# zx80_SD_12_smd_build006_5_STM32.net
KiCad netlist of a schematic drawn in EAGLE
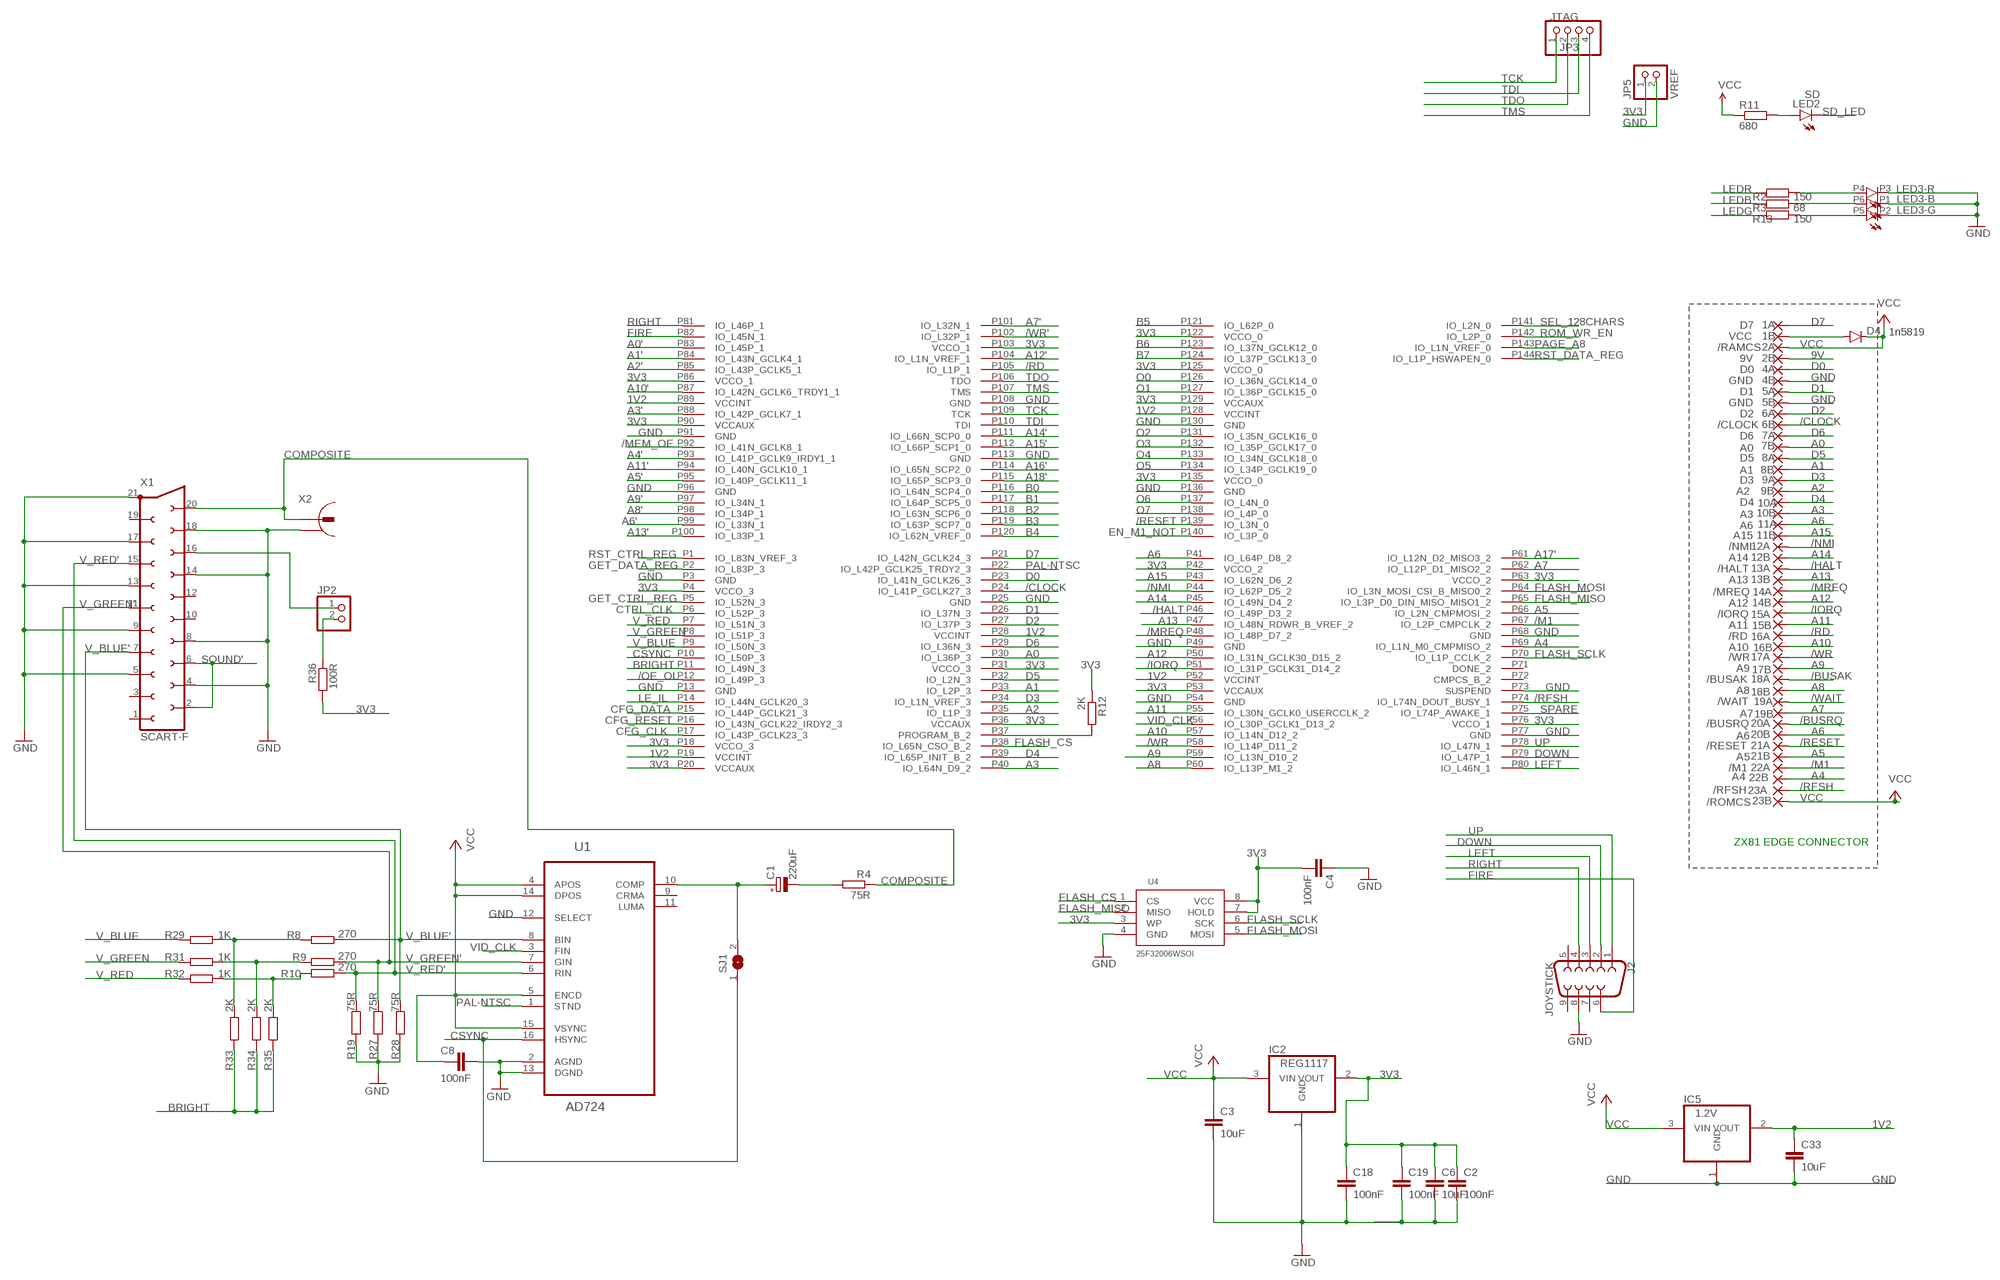
[diagram p0: schematic, sheet 1, part 1 of 2]
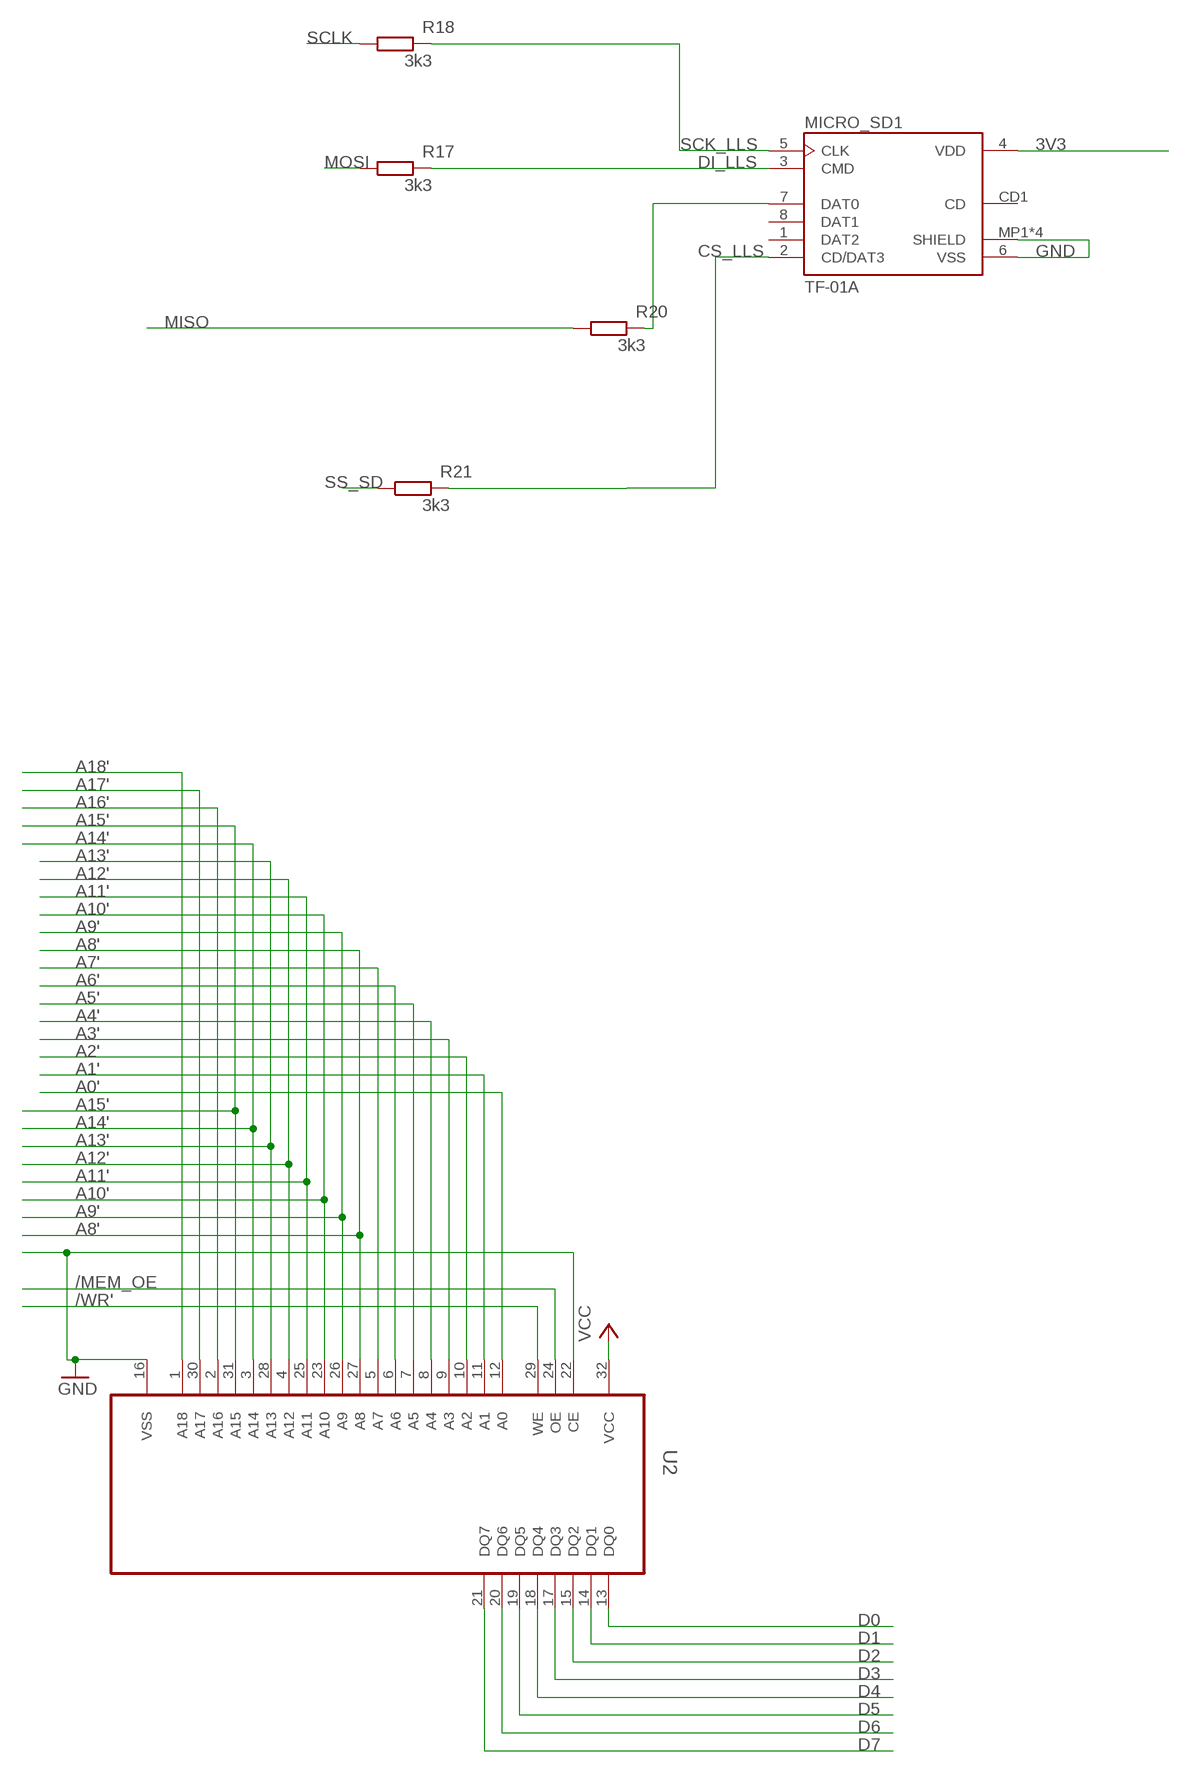
[diagram p1: schematic, sheet 1, part 2 of 2]
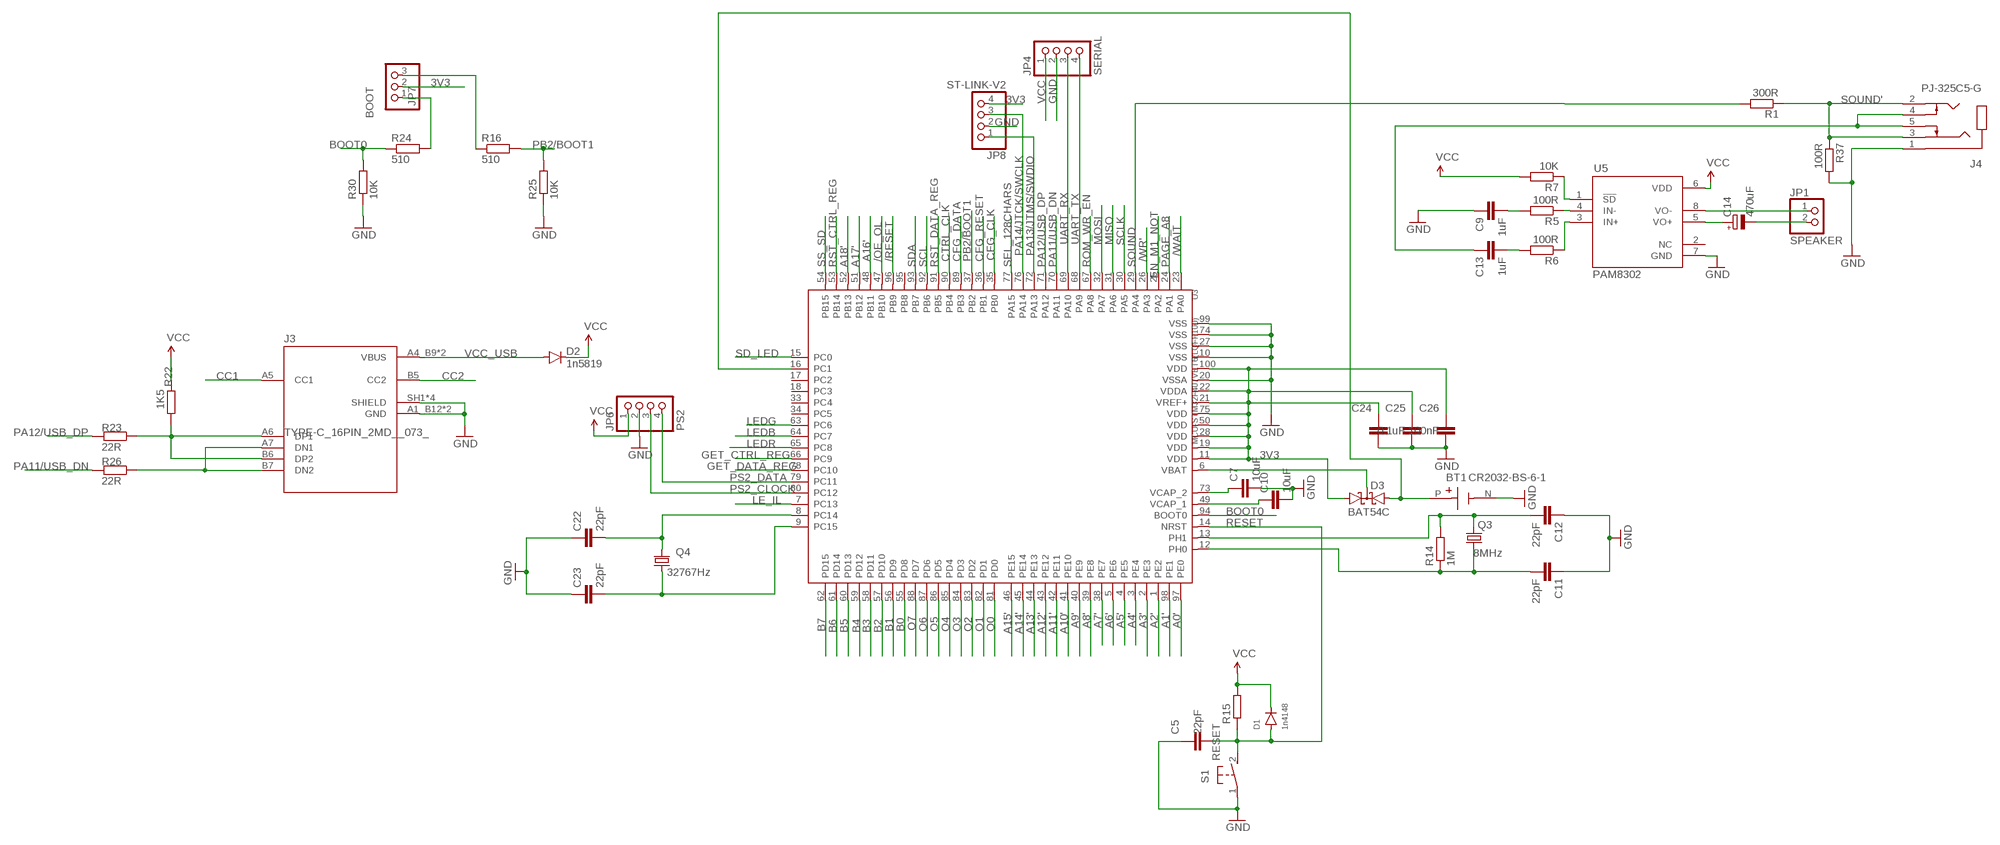
[diagram p2: schematic, sheet 2]

(export (version "E")
  (design (tool "Eeschema 10.0.6"))
  (components
    (comp (ref "BT1")
      (value "CR2032-BS-6-1")
      (footprint "eagle-import:BAT_CR2032-BS-6-1")
      (fields (field (name "MF") "Shenzhen Q&J Electronics Co. Ltd"))
      (libsource (lib "eagle-import") (part "CR2032-BS-6-1"))
    )
    (comp (ref "C5")
      (value "22pF")
      (footprint "eagle-import:C0603")
      (libsource (lib "eagle-import") (part "C-EUC0603"))
    )
    (comp (ref "C7")
      (value "10uF")
      (footprint "eagle-import:C0603")
      (libsource (lib "eagle-import") (part "C-EUC0603"))
    )
    (comp (ref "C9")
      (value "1uF")
      (footprint "eagle-import:C0603")
      (libsource (lib "eagle-import") (part "C-EUC0603"))
    )
    (comp (ref "C10")
      (value "10uF")
      (footprint "eagle-import:C0603")
      (libsource (lib "eagle-import") (part "C-EUC0603"))
    )
    (comp (ref "C11")
      (value "22pF")
      (footprint "eagle-import:C0603")
      (libsource (lib "eagle-import") (part "C-EUC0603"))
    )
    (comp (ref "C12")
      (value "22pF")
      (footprint "eagle-import:C0603")
      (libsource (lib "eagle-import") (part "C-EUC0603"))
    )
    (comp (ref "C13")
      (value "1uF")
      (footprint "eagle-import:C0603")
      (libsource (lib "eagle-import") (part "C-EUC0603"))
    )
    (comp (ref "C14")
      (value "470uF")
      (footprint "eagle-import:UD-6,3X7,7_NICHICON")
      (libsource (lib "eagle-import") (part "CPOL-EUUD-6,3X7,7"))
    )
    (comp (ref "C22")
      (value "22pF")
      (footprint "eagle-import:C0603")
      (libsource (lib "eagle-import") (part "C-EUC0603"))
    )
    (comp (ref "C23")
      (value "22pF")
      (footprint "eagle-import:C0603")
      (libsource (lib "eagle-import") (part "C-EUC0603"))
    )
    (comp (ref "C24")
      (value "0.1uF")
      (footprint "eagle-import:C0603")
      (libsource (lib "eagle-import") (part "C-EUC0603"))
    )
    (comp (ref "C25")
      (value "0.1uF")
      (footprint "eagle-import:C0603")
      (libsource (lib "eagle-import") (part "C-EUC0603"))
    )
    (comp (ref "C26")
      (value "100nF")
      (footprint "eagle-import:C0603")
      (libsource (lib "eagle-import") (part "C-EUC0603"))
    )
    (comp (ref "D1")
      (value "1n4148")
      (footprint "eagle-import:SOD123")
      (libsource (lib "eagle-import") (part "DIODE-SOD123"))
    )
    (comp (ref "D2")
      (value "1n5819")
      (footprint "eagle-import:SOD323-W")
      (libsource (lib "eagle-import") (part "DIODE-SOD323-W"))
    )
    (comp (ref "D3")
      (value "BAT54C")
      (footprint "eagle-import:SOT23")
      (libsource (lib "eagle-import") (part "BAT54C"))
    )
    (comp (ref "J3")
      (value "TYPE-C_16PIN_2MD__073_")
      (footprint "eagle-import:SHOUHAN_TYPE-C_16PIN_2MD__073_")
      (fields (field (name "MF") "Shouhan") (field (name "MP") "TYPE-C 16PIN 2MD (073)"))
      (libsource (lib "eagle-import") (part "TYPE-C_16PIN_2MD__073_"))
    )
    (comp (ref "J4")
      (value "PJ-325C5-G")
      (footprint "eagle-import:XKB_PJ-325C5-G")
      (fields (field (name "MF") "XKB Connection"))
      (libsource (lib "eagle-import") (part "PJ-325C5-G"))
    )
    (comp (ref "JP1")
      (value "SPEAKER")
      (footprint "eagle-import:1X02")
      (libsource (lib "eagle-import") (part "PINHD-1X2"))
    )
    (comp (ref "JP4")
      (value "SERIAL")
      (footprint "eagle-import:1X04")
      (libsource (lib "eagle-import") (part "PINHD-1X4"))
    )
    (comp (ref "JP6")
      (value "PS2")
      (footprint "eagle-import:1X04")
      (libsource (lib "eagle-import") (part "PINHD-1X4"))
    )
    (comp (ref "JP7")
      (value "BOOT")
      (footprint "eagle-import:1X03")
      (libsource (lib "eagle-import") (part "PINHD-1X3"))
    )
    (comp (ref "JP8")
      (value "ST-LINK-V2")
      (footprint "eagle-import:1X04")
      (libsource (lib "eagle-import") (part "PINHD-1X4"))
    )
    (comp (ref "Q3")
      (value "8MHz")
      (footprint "eagle-import:3.2X2.5_KX-7")
      (libsource (lib "eagle-import") (part "KX-7"))
    )
    (comp (ref "Q4")
      (value "32767Hz")
      (footprint "eagle-import:3.2X1.5")
      (libsource (lib "eagle-import") (part "KX-327-NHT"))
    )
    (comp (ref "R1")
      (value "300R")
      (footprint "eagle-import:R0603")
      (libsource (lib "eagle-import") (part "R-EU_R0603"))
    )
    (comp (ref "R5")
      (value "100R")
      (footprint "eagle-import:R0603")
      (libsource (lib "eagle-import") (part "R-EU_R0603"))
    )
    (comp (ref "R6")
      (value "100R")
      (footprint "eagle-import:R0603")
      (libsource (lib "eagle-import") (part "R-EU_R0603"))
    )
    (comp (ref "R7")
      (value "10K")
      (footprint "eagle-import:R0603")
      (libsource (lib "eagle-import") (part "R-EU_R0603"))
    )
    (comp (ref "R14")
      (value "1M")
      (footprint "eagle-import:R0402")
      (libsource (lib "eagle-import") (part "R-EU_R0402"))
    )
    (comp (ref "R15")
      (value "3k3")
      (footprint "eagle-import:R0603")
      (libsource (lib "eagle-import") (part "R-EU_R0603"))
    )
    (comp (ref "R16")
      (value "510")
      (footprint "eagle-import:R0603")
      (libsource (lib "eagle-import") (part "R-EU_R0603"))
    )
    (comp (ref "R22")
      (value "1K5")
      (footprint "eagle-import:R0603")
      (libsource (lib "eagle-import") (part "R-EU_R0603"))
    )
    (comp (ref "R23")
      (value "22R")
      (footprint "eagle-import:R0603")
      (libsource (lib "eagle-import") (part "R-EU_R0603"))
    )
    (comp (ref "R24")
      (value "510")
      (footprint "eagle-import:R0603")
      (libsource (lib "eagle-import") (part "R-EU_R0603"))
    )
    (comp (ref "R25")
      (value "10K")
      (footprint "eagle-import:R0603")
      (libsource (lib "eagle-import") (part "R-EU_R0603"))
    )
    (comp (ref "R26")
      (value "22R")
      (footprint "eagle-import:R0603")
      (libsource (lib "eagle-import") (part "R-EU_R0603"))
    )
    (comp (ref "R30")
      (value "10K")
      (footprint "eagle-import:R0603")
      (libsource (lib "eagle-import") (part "R-EU_R0603"))
    )
    (comp (ref "R37")
      (value "100R")
      (footprint "eagle-import:R0603")
      (libsource (lib "eagle-import") (part "R-EU_R0603"))
    )
    (comp (ref "S1")
      (value "RESET")
      (footprint "eagle-import:B3F-31XX")
      (fields (field (name "MPN") "B3F-3100"))
      (libsource (lib "eagle-import") (part "31-XX"))
    )
    (comp (ref "U3")
      (value "MCU-STM32F407VET6(LQFP100)")
      (footprint "eagle-import:LQFP100-0.5-13.8X13.8MM")
      (fields (field (name "MF") "STMicroelectronics") (field (name "MP") "STM32F407VET6"))
      (libsource (lib "eagle-import") (part "MCU-STM32F407VET6(LQFP100)"))
    )
    (comp (ref "U5")
      (value "PAM8302")
      (footprint "eagle-import:SOIC127P600X170-8N")
      (fields (field (name "MF") "Diodes Inc.") (field (name "MP") "PAM8302AADCR"))
      (libsource (lib "eagle-import") (part "PAM8302AADCR"))
    )
    (comp (ref "1A")
      (value "D7")
      (footprint "eagle-import:EDGEPIN")
      (libsource (lib "eagle-import") (part "SMD2EDGEPIN"))
    )
    (comp (ref "1B")
      (value "VCC")
      (footprint "eagle-import:EDGEPIN")
      (libsource (lib "eagle-import") (part "SMD2EDGEPIN"))
    )
    (comp (ref "2A")
      (value "/RAMCS")
      (footprint "eagle-import:EDGEPIN")
      (libsource (lib "eagle-import") (part "SMD2EDGEPIN"))
    )
    (comp (ref "2B")
      (value "9V")
      (footprint "eagle-import:EDGEPIN")
      (libsource (lib "eagle-import") (part "SMD2EDGEPIN"))
    )
    (comp (ref "4A")
      (value "D0")
      (footprint "eagle-import:EDGEPIN")
      (libsource (lib "eagle-import") (part "SMD2EDGEPIN"))
    )
    (comp (ref "4B")
      (value "GND")
      (footprint "eagle-import:EDGEPIN")
      (libsource (lib "eagle-import") (part "SMD2EDGEPIN"))
    )
    (comp (ref "5A")
      (value "D1")
      (footprint "eagle-import:EDGEPIN")
      (libsource (lib "eagle-import") (part "SMD2EDGEPIN"))
    )
    (comp (ref "5B")
      (value "GND")
      (footprint "eagle-import:EDGEPIN")
      (libsource (lib "eagle-import") (part "SMD2EDGEPIN"))
    )
    (comp (ref "6A")
      (value "D2")
      (footprint "eagle-import:EDGEPIN")
      (libsource (lib "eagle-import") (part "SMD2EDGEPIN"))
    )
    (comp (ref "6B")
      (value "/CLOCK")
      (footprint "eagle-import:EDGEPIN")
      (libsource (lib "eagle-import") (part "SMD2EDGEPIN"))
    )
    (comp (ref "7A")
      (value "D6")
      (footprint "eagle-import:EDGEPIN")
      (libsource (lib "eagle-import") (part "SMD2EDGEPIN"))
    )
    (comp (ref "7B")
      (value "A0")
      (footprint "eagle-import:EDGEPIN")
      (libsource (lib "eagle-import") (part "SMD2EDGEPIN"))
    )
    (comp (ref "8A")
      (value "D5")
      (footprint "eagle-import:EDGEPIN")
      (libsource (lib "eagle-import") (part "SMD2EDGEPIN"))
    )
    (comp (ref "8B")
      (value "A1")
      (footprint "eagle-import:EDGEPIN")
      (libsource (lib "eagle-import") (part "SMD2EDGEPIN"))
    )
    (comp (ref "9A")
      (value "D3")
      (footprint "eagle-import:EDGEPIN")
      (libsource (lib "eagle-import") (part "SMD2EDGEPIN"))
    )
    (comp (ref "9B")
      (value "A2")
      (footprint "eagle-import:EDGEPIN")
      (libsource (lib "eagle-import") (part "SMD2EDGEPIN"))
    )
    (comp (ref "10A")
      (value "D4")
      (footprint "eagle-import:EDGEPIN")
      (libsource (lib "eagle-import") (part "SMD2EDGEPIN"))
    )
    (comp (ref "10B")
      (value "A3")
      (footprint "eagle-import:EDGEPIN")
      (libsource (lib "eagle-import") (part "SMD2EDGEPIN"))
    )
    (comp (ref "11A")
      (value "A6")
      (footprint "eagle-import:EDGEPIN")
      (libsource (lib "eagle-import") (part "SMD2EDGEPIN"))
    )
    (comp (ref "11B")
      (value "A15")
      (footprint "eagle-import:EDGEPIN")
      (libsource (lib "eagle-import") (part "SMD2EDGEPIN"))
    )
    (comp (ref "12A")
      (value "/NMI")
      (footprint "eagle-import:EDGEPIN")
      (libsource (lib "eagle-import") (part "SMD2EDGEPIN"))
    )
    (comp (ref "12B")
      (value "A14")
      (footprint "eagle-import:EDGEPIN")
      (libsource (lib "eagle-import") (part "SMD2EDGEPIN"))
    )
    (comp (ref "13A")
      (value "/HALT")
      (footprint "eagle-import:EDGEPIN")
      (libsource (lib "eagle-import") (part "SMD2EDGEPIN"))
    )
    (comp (ref "13B")
      (value "A13")
      (footprint "eagle-import:EDGEPIN")
      (libsource (lib "eagle-import") (part "SMD2EDGEPIN"))
    )
    (comp (ref "14A")
      (value "/MREQ")
      (footprint "eagle-import:EDGEPIN")
      (libsource (lib "eagle-import") (part "SMD2EDGEPIN"))
    )
    (comp (ref "14B")
      (value "A12")
      (footprint "eagle-import:EDGEPIN")
      (libsource (lib "eagle-import") (part "SMD2EDGEPIN"))
    )
    (comp (ref "15A")
      (value "/IORQ")
      (footprint "eagle-import:EDGEPIN")
      (libsource (lib "eagle-import") (part "SMD2EDGEPIN"))
    )
    (comp (ref "15B")
      (value "A11")
      (footprint "eagle-import:EDGEPIN")
      (libsource (lib "eagle-import") (part "SMD2EDGEPIN"))
    )
    (comp (ref "16A")
      (value "/RD")
      (footprint "eagle-import:EDGEPIN")
      (libsource (lib "eagle-import") (part "SMD2EDGEPIN"))
    )
    (comp (ref "16B")
      (value "A10")
      (footprint "eagle-import:EDGEPIN")
      (libsource (lib "eagle-import") (part "SMD2EDGEPIN"))
    )
    (comp (ref "17A")
      (value "/WR")
      (footprint "eagle-import:EDGEPIN")
      (libsource (lib "eagle-import") (part "SMD2EDGEPIN"))
    )
    (comp (ref "17B")
      (value "A9")
      (footprint "eagle-import:EDGEPIN")
      (libsource (lib "eagle-import") (part "SMD2EDGEPIN"))
    )
    (comp (ref "18A")
      (value "/BUSAK")
      (footprint "eagle-import:EDGEPIN")
      (libsource (lib "eagle-import") (part "SMD2EDGEPIN"))
    )
    (comp (ref "18B")
      (value "A8")
      (footprint "eagle-import:EDGEPIN")
      (libsource (lib "eagle-import") (part "SMD2EDGEPIN"))
    )
    (comp (ref "19A")
      (value "/WAIT")
      (footprint "eagle-import:EDGEPIN")
      (libsource (lib "eagle-import") (part "SMD2EDGEPIN"))
    )
    (comp (ref "19B")
      (value "A7")
      (footprint "eagle-import:EDGEPIN")
      (libsource (lib "eagle-import") (part "SMD2EDGEPIN"))
    )
    (comp (ref "20A")
      (value "/BUSRQ")
      (footprint "eagle-import:EDGEPIN")
      (libsource (lib "eagle-import") (part "SMD2EDGEPIN"))
    )
    (comp (ref "20B")
      (value "A6")
      (footprint "eagle-import:EDGEPIN")
      (libsource (lib "eagle-import") (part "SMD2EDGEPIN"))
    )
    (comp (ref "21A")
      (value "/RESET")
      (footprint "eagle-import:EDGEPIN")
      (libsource (lib "eagle-import") (part "SMD2EDGEPIN"))
    )
    (comp (ref "21B")
      (value "A5")
      (footprint "eagle-import:EDGEPIN")
      (libsource (lib "eagle-import") (part "SMD2EDGEPIN"))
    )
    (comp (ref "22A")
      (value "/M1")
      (footprint "eagle-import:EDGEPIN")
      (libsource (lib "eagle-import") (part "SMD2EDGEPIN"))
    )
    (comp (ref "22B")
      (value "A4")
      (footprint "eagle-import:EDGEPIN")
      (libsource (lib "eagle-import") (part "SMD2EDGEPIN"))
    )
    (comp (ref "23A")
      (value "/RFSH")
      (footprint "eagle-import:EDGEPIN")
      (libsource (lib "eagle-import") (part "SMD2EDGEPIN"))
    )
    (comp (ref "23B")
      (value "/ROMCS")
      (footprint "eagle-import:EDGEPIN")
      (libsource (lib "eagle-import") (part "SMD2EDGEPIN"))
    )
    (comp (ref "C1")
      (value "220uF")
      (footprint "eagle-import:UD-6,3X7,7_NICHICON")
      (libsource (lib "eagle-import") (part "CPOL-EUUD-6,3X7,7"))
    )
    (comp (ref "C2")
      (value "100nF")
      (footprint "eagle-import:C0603")
      (libsource (lib "eagle-import") (part "C-EUC0603"))
    )
    (comp (ref "C3")
      (value "10uF")
      (footprint "eagle-import:C0603")
      (libsource (lib "eagle-import") (part "C-EUC0603"))
    )
    (comp (ref "C4")
      (value "100nF")
      (footprint "eagle-import:C0603")
      (libsource (lib "eagle-import") (part "C-EUC0603"))
    )
    (comp (ref "C6")
      (value "10uF")
      (footprint "eagle-import:C0603")
      (libsource (lib "eagle-import") (part "C-EUC0603"))
    )
    (comp (ref "C8")
      (value "100nF")
      (footprint "eagle-import:C0603K")
      (libsource (lib "eagle-import") (part "C-EUC0603K"))
    )
    (comp (ref "C18")
      (value "100nF")
      (footprint "eagle-import:C0603")
      (libsource (lib "eagle-import") (part "C-EUC0603"))
    )
    (comp (ref "C19")
      (value "100nF")
      (footprint "eagle-import:C0603")
      (libsource (lib "eagle-import") (part "C-EUC0603"))
    )
    (comp (ref "C33")
      (value "10uF")
      (footprint "eagle-import:C0603")
      (libsource (lib "eagle-import") (part "C-EUC0603"))
    )
    (comp (ref "D4")
      (value "1n5819")
      (footprint "eagle-import:SOD323-W")
      (libsource (lib "eagle-import") (part "DIODE-SOD323-W"))
    )
    (comp (ref "IC2")
      (value "REG1117")
      (footprint "eagle-import:SOT223")
      (libsource (lib "eagle-import") (part "REG1117"))
    )
    (comp (ref "IC5")
      (value "1.2V")
      (footprint "eagle-import:SOT223")
      (fields (field (name "MPN") "REG1117"))
      (libsource (lib "eagle-import") (part "REG1117"))
    )
    (comp (ref "J2")
      (value "JOYSTICK")
      (footprint "eagle-import:DB9_MALE")
      (libsource (lib "eagle-import") (part "DB9MALE"))
    )
    (comp (ref "JP2")
      (value "PINHD-1X2")
      (footprint "eagle-import:1X02")
      (libsource (lib "eagle-import") (part "PINHD-1X2"))
    )
    (comp (ref "JP3")
      (value "JTAG")
      (footprint "eagle-import:1X04")
      (libsource (lib "eagle-import") (part "PINHD-1X4"))
    )
    (comp (ref "JP5")
      (value "VREF")
      (footprint "eagle-import:1X02")
      (libsource (lib "eagle-import") (part "PINHD-1X2"))
    )
    (comp (ref "LED2")
      (value "SD")
      (footprint "eagle-import:CHIPLED_0805")
      (libsource (lib "eagle-import") (part "LEDCHIPLED_0805"))
    )
    (comp (ref "LED3")
      (value "STATUS")
      (footprint "eagle-import:3535-PLCC6")
      (libsource (lib "eagle-import") (part "3535RGB3535RGB"))
    )
    (comp (ref "MICRO_SD1")
      (value "TF-01A")
      (footprint "eagle-import:TF-01A")
      (fields (field (name "MF") "HRO Electronics Co., Ltd."))
      (libsource (lib "eagle-import") (part "TF-01A"))
    )
    (comp (ref "R2")
      (value "150")
      (footprint "eagle-import:R0603")
      (libsource (lib "eagle-import") (part "R-EU_R0603"))
    )
    (comp (ref "R3")
      (value "68")
      (footprint "eagle-import:R0603")
      (libsource (lib "eagle-import") (part "R-EU_R0603"))
    )
    (comp (ref "R4")
      (value "75R")
      (footprint "eagle-import:R0603")
      (libsource (lib "eagle-import") (part "R-EU_R0603"))
    )
    (comp (ref "R8")
      (value "270")
      (footprint "eagle-import:R0603")
      (libsource (lib "eagle-import") (part "R-EU_R0603"))
    )
    (comp (ref "R9")
      (value "270")
      (footprint "eagle-import:R0603")
      (libsource (lib "eagle-import") (part "R-EU_R0603"))
    )
    (comp (ref "R10")
      (value "270")
      (footprint "eagle-import:R0603")
      (libsource (lib "eagle-import") (part "R-EU_R0603"))
    )
    (comp (ref "R11")
      (value "680")
      (footprint "eagle-import:R0603")
      (libsource (lib "eagle-import") (part "R-EU_R0603"))
    )
    (comp (ref "R12")
      (value "2K")
      (footprint "eagle-import:R0402")
      (libsource (lib "eagle-import") (part "R-EU_R0402"))
    )
    (comp (ref "R13")
      (value "150")
      (footprint "eagle-import:R0603")
      (libsource (lib "eagle-import") (part "R-EU_R0603"))
    )
    (comp (ref "R17")
      (value "3k3")
      (footprint "eagle-import:R0603")
      (libsource (lib "eagle-import") (part "R-EU_R0603"))
    )
    (comp (ref "R18")
      (value "3k3")
      (footprint "eagle-import:R0603")
      (libsource (lib "eagle-import") (part "R-EU_R0603"))
    )
    (comp (ref "R19")
      (value "75R")
      (footprint "eagle-import:R0603")
      (libsource (lib "eagle-import") (part "R-EU_R0603"))
    )
    (comp (ref "R20")
      (value "3k3")
      (footprint "eagle-import:R0603")
      (libsource (lib "eagle-import") (part "R-EU_R0603"))
    )
    (comp (ref "R21")
      (value "3k3")
      (footprint "eagle-import:R0603")
      (libsource (lib "eagle-import") (part "R-EU_R0603"))
    )
    (comp (ref "R27")
      (value "75R")
      (footprint "eagle-import:R0603")
      (libsource (lib "eagle-import") (part "R-EU_R0603"))
    )
    (comp (ref "R28")
      (value "75R")
      (footprint "eagle-import:R0603")
      (libsource (lib "eagle-import") (part "R-EU_R0603"))
    )
    (comp (ref "R29")
      (value "1K")
      (footprint "eagle-import:R0402")
      (libsource (lib "eagle-import") (part "R-EU_R0402"))
    )
    (comp (ref "R31")
      (value "1K")
      (footprint "eagle-import:R0402")
      (libsource (lib "eagle-import") (part "R-EU_R0402"))
    )
    (comp (ref "R32")
      (value "1K")
      (footprint "eagle-import:R0402")
      (libsource (lib "eagle-import") (part "R-EU_R0402"))
    )
    (comp (ref "R33")
      (value "2K")
      (footprint "eagle-import:R0402")
      (libsource (lib "eagle-import") (part "R-EU_R0402"))
    )
    (comp (ref "R34")
      (value "2K")
      (footprint "eagle-import:R0402")
      (libsource (lib "eagle-import") (part "R-EU_R0402"))
    )
    (comp (ref "R35")
      (value "2K")
      (footprint "eagle-import:R0402")
      (libsource (lib "eagle-import") (part "R-EU_R0402"))
    )
    (comp (ref "R36")
      (value "100R")
      (footprint "eagle-import:R0603")
      (libsource (lib "eagle-import") (part "R-EU_R0603"))
    )
    (comp (ref "SJ1") (value "SJ") (footprint "eagle-import:SJ") (libsource (lib "eagle-import") (part "SJ")))
    (comp (ref "U1")
      (value "AD724")
      (footprint "eagle-import:SOIC127P1032X265-16N")
      (fields (field (name "MF") "Analog Devices") (field (name "MP") "AD724JR"))
      (libsource (lib "eagle-import") (part "AD724JRZ"))
    )
    (comp (ref "U2")
      (value "AS6C4008")
      (footprint "eagle-import:SOP32-5")
      (libsource (lib "eagle-import") (part "AS6C4008-55SINSOP5"))
    )
    (comp (ref "U4")
      (value "25F32006WSOI")
      (footprint "eagle-import:SO08-EIAJ")
      (libsource (lib "eagle-import") (part "SPI_FLASH-X25XXSMD1"))
    )
    (comp (ref "U6")
      (value "XC6SLX9-2TQG144C")
      (footprint "eagle-import:TQ144")
      (fields (field (name "MF") "Xilinx Inc."))
      (libsource (lib "eagle-import") (part "XC6SLX9-2TQG144C"))
    )
    (comp (ref "X1")
      (value "SCART-F")
      (footprint "eagle-import:SCART-F")
      (libsource (lib "eagle-import") (part "SCART-F"))
    )
    (comp (ref "X2")
      (value "CON-CONRAD_736880-2P")
      (footprint "eagle-import:3P")
      (libsource (lib "eagle-import") (part "CON-CONRAD_736880-2P"))
    )
  )
  (nets
    (net (code "1") (name "1V2") (class "Default")
      (node (ref "C33") (pin "1") (pinfunction "1_1") (pintype "passive"))
      (node (ref "IC5") (pin "2") (pinfunction "VOUT_2") (pintype "output"))
      (node (ref "U6") (pin "P128") (pinfunction "VCCINT_P128") (pintype "bidirectional"))
      (node (ref "U6") (pin "P19") (pinfunction "VCCINT_P19") (pintype "bidirectional"))
      (node (ref "U6") (pin "P28") (pinfunction "VCCINT_P28") (pintype "bidirectional"))
      (node (ref "U6") (pin "P52") (pinfunction "VCCINT_P52") (pintype "bidirectional"))
      (node (ref "U6") (pin "P89") (pinfunction "VCCINT_P89") (pintype "bidirectional"))
    )
    (net (code "2") (name "3V3") (class "Default")
      (node (ref "C18") (pin "1") (pinfunction "1_1") (pintype "passive"))
      (node (ref "C19") (pin "1") (pinfunction "1_1") (pintype "passive"))
      (node (ref "C2") (pin "1") (pinfunction "1_1") (pintype "passive"))
      (node (ref "C24") (pin "1") (pinfunction "1_1") (pintype "passive"))
      (node (ref "C25") (pin "1") (pinfunction "1_1") (pintype "passive"))
      (node (ref "C26") (pin "1") (pinfunction "1_1") (pintype "passive"))
      (node (ref "C4") (pin "2") (pinfunction "2_2") (pintype "passive"))
      (node (ref "C6") (pin "1") (pinfunction "1_1") (pintype "passive"))
      (node (ref "D3") (pin "1") (pinfunction "A1_1") (pintype "passive"))
      (node (ref "IC2") (pin "2") (pinfunction "VOUT_2") (pintype "output"))
      (node (ref "JP5") (pin "1") (pinfunction "1_1") (pintype "passive"))
      (node (ref "JP7") (pin "2") (pinfunction "2_2") (pintype "passive"))
      (node (ref "JP8") (pin "4") (pinfunction "4_4") (pintype "passive"))
      (node (ref "MICRO_SD1") (pin "4") (pinfunction "VDD_4") (pintype "power_in"))
      (node (ref "R12") (pin "1") (pinfunction "1_1") (pintype "passive"))
      (node (ref "R36") (pin "2") (pinfunction "2_2") (pintype "passive"))
      (node (ref "U3") (pin "100") (pinfunction "VDD_100") (pintype "bidirectional"))
      (node (ref "U3") (pin "11") (pinfunction "VDD_11") (pintype "bidirectional"))
      (node (ref "U3") (pin "19") (pinfunction "VDD_19") (pintype "bidirectional"))
      (node (ref "U3") (pin "21") (pinfunction "VREF+_21") (pintype "bidirectional"))
      (node (ref "U3") (pin "22") (pinfunction "VDDA_22") (pintype "bidirectional"))
      (node (ref "U3") (pin "28") (pinfunction "VDD_28") (pintype "bidirectional"))
      (node (ref "U3") (pin "50") (pinfunction "VDD_50") (pintype "bidirectional"))
      (node (ref "U3") (pin "75") (pinfunction "VDD_75") (pintype "bidirectional"))
      (node (ref "U4") (pin "3") (pinfunction "WP_3") (pintype "bidirectional"))
      (node (ref "U4") (pin "7") (pinfunction "HOLD_7") (pintype "bidirectional"))
      (node (ref "U4") (pin "8") (pinfunction "VCC_8") (pintype "power_in"))
      (node (ref "U6") (pin "P103") (pinfunction "VCCO_1_P103") (pintype "bidirectional"))
      (node (ref "U6") (pin "P122") (pinfunction "VCCO_0_P122") (pintype "bidirectional"))
      (node (ref "U6") (pin "P125") (pinfunction "VCCO_0_P125") (pintype "bidirectional"))
      (node (ref "U6") (pin "P129") (pinfunction "VCCAUX_P129") (pintype "bidirectional"))
      (node (ref "U6") (pin "P135") (pinfunction "VCCO_0_P135") (pintype "bidirectional"))
      (node (ref "U6") (pin "P18") (pinfunction "VCCO_3_P18") (pintype "bidirectional"))
      (node (ref "U6") (pin "P20") (pinfunction "VCCAUX_P20") (pintype "bidirectional"))
      (node (ref "U6") (pin "P31") (pinfunction "VCCO_3_P31") (pintype "bidirectional"))
      (node (ref "U6") (pin "P36") (pinfunction "VCCAUX_P36") (pintype "bidirectional"))
      (node (ref "U6") (pin "P4") (pinfunction "VCCO_3_P4") (pintype "bidirectional"))
      (node (ref "U6") (pin "P42") (pinfunction "VCCO_2_P42") (pintype "bidirectional"))
      (node (ref "U6") (pin "P53") (pinfunction "VCCAUX_P53") (pintype "bidirectional"))
      (node (ref "U6") (pin "P63") (pinfunction "VCCO_2_P63") (pintype "bidirectional"))
      (node (ref "U6") (pin "P76") (pinfunction "VCCO_1_P76") (pintype "bidirectional"))
      (node (ref "U6") (pin "P86") (pinfunction "VCCO_1_P86") (pintype "bidirectional"))
      (node (ref "U6") (pin "P90") (pinfunction "VCCAUX_P90") (pintype "bidirectional"))
    )
    (net (code "3") (name "9V") (class "Default")
      (node (ref "2B") (pin "1") (pinfunction "P_1") (pintype "passive"))
    )
    (net (code "4") (name "A0") (class "Default")
      (node (ref "7B") (pin "1") (pinfunction "P_1") (pintype "passive"))
      (node (ref "U6") (pin "P30") (pinfunction "IO_L36P_3_P30") (pintype "bidirectional"))
    )
    (net (code "5") (name "A0'") (class "Default")
      (node (ref "U2") (pin "12") (pinfunction "A0_12") (pintype "input"))
      (node (ref "U3") (pin "97") (pinfunction "PE0_97") (pintype "bidirectional"))
      (node (ref "U6") (pin "P83") (pinfunction "IO_L45P_1_P83") (pintype "bidirectional"))
    )
    (net (code "6") (name "A1") (class "Default")
      (node (ref "8B") (pin "1") (pinfunction "P_1") (pintype "passive"))
      (node (ref "U6") (pin "P33") (pinfunction "IO_L2P_3_P33") (pintype "bidirectional"))
    )
    (net (code "7") (name "A1'") (class "Default")
      (node (ref "U2") (pin "11") (pinfunction "A1_11") (pintype "input"))
      (node (ref "U3") (pin "98") (pinfunction "PE1_98") (pintype "bidirectional"))
      (node (ref "U6") (pin "P84") (pinfunction "IO_L43N_GCLK4_1_P84") (pintype "bidirectional"))
    )
    (net (code "8") (name "A2") (class "Default")
      (node (ref "9B") (pin "1") (pinfunction "P_1") (pintype "passive"))
      (node (ref "U6") (pin "P35") (pinfunction "IO_L1P_3_P35") (pintype "bidirectional"))
    )
    (net (code "9") (name "A2'") (class "Default")
      (node (ref "U2") (pin "10") (pinfunction "A2_10") (pintype "input"))
      (node (ref "U3") (pin "1") (pinfunction "PE2_1") (pintype "bidirectional"))
      (node (ref "U6") (pin "P85") (pinfunction "IO_L43P_GCLK5_1_P85") (pintype "bidirectional"))
    )
    (net (code "10") (name "A3") (class "Default")
      (node (ref "10B") (pin "1") (pinfunction "P_1") (pintype "passive"))
      (node (ref "U6") (pin "P40") (pinfunction "IO_L64N_D9_2_P40") (pintype "bidirectional"))
    )
    (net (code "11") (name "A3'") (class "Default")
      (node (ref "U2") (pin "9") (pinfunction "A3_9") (pintype "input"))
      (node (ref "U3") (pin "2") (pinfunction "PE3_2") (pintype "bidirectional"))
      (node (ref "U6") (pin "P88") (pinfunction "IO_L42P_GCLK7_1_P88") (pintype "bidirectional"))
    )
    (net (code "12") (name "A4") (class "Default")
      (node (ref "22B") (pin "1") (pinfunction "P_1") (pintype "passive"))
      (node (ref "U6") (pin "P69") (pinfunction "IO_L1N_M0_CMPMISO_2_P69") (pintype "bidirectional"))
    )
    (net (code "13") (name "A4'") (class "Default")
      (node (ref "U2") (pin "8") (pinfunction "A4_8") (pintype "input"))
      (node (ref "U3") (pin "3") (pinfunction "PE4_3") (pintype "bidirectional"))
      (node (ref "U6") (pin "P93") (pinfunction "IO_L41P_GCLK9_IRDY1_1_P93") (pintype "bidirectional"))
    )
    (net (code "14") (name "A5") (class "Default")
      (node (ref "21B") (pin "1") (pinfunction "P_1") (pintype "passive"))
      (node (ref "U6") (pin "P66") (pinfunction "IO_L2N_CMPMOSI_2_P66") (pintype "bidirectional"))
    )
    (net (code "15") (name "A5'") (class "Default")
      (node (ref "U2") (pin "7") (pinfunction "A5_7") (pintype "input"))
      (node (ref "U3") (pin "4") (pinfunction "PE5_4") (pintype "bidirectional"))
      (node (ref "U6") (pin "P95") (pinfunction "IO_L40P_GCLK11_1_P95") (pintype "bidirectional"))
    )
    (net (code "16") (name "A6") (class "Default")
      (node (ref "11A") (pin "1") (pinfunction "P_1") (pintype "passive"))
      (node (ref "20B") (pin "1") (pinfunction "P_1") (pintype "passive"))
      (node (ref "U6") (pin "P41") (pinfunction "IO_L64P_D8_2_P41") (pintype "bidirectional"))
    )
    (net (code "17") (name "A6'") (class "Default")
      (node (ref "U2") (pin "6") (pinfunction "A6_6") (pintype "input"))
      (node (ref "U3") (pin "5") (pinfunction "PE6_5") (pintype "bidirectional"))
      (node (ref "U6") (pin "P99") (pinfunction "IO_L33N_1_P99") (pintype "bidirectional"))
    )
    (net (code "18") (name "A7") (class "Default")
      (node (ref "19B") (pin "1") (pinfunction "P_1") (pintype "passive"))
      (node (ref "U6") (pin "P62") (pinfunction "IO_L12P_D1_MISO2_2_P62") (pintype "bidirectional"))
    )
    (net (code "19") (name "A7'") (class "Default")
      (node (ref "U2") (pin "5") (pinfunction "A7_5") (pintype "input"))
      (node (ref "U3") (pin "38") (pinfunction "PE7_38") (pintype "bidirectional"))
      (node (ref "U6") (pin "P101") (pinfunction "IO_L32N_1_P101") (pintype "bidirectional"))
    )
    (net (code "20") (name "A8") (class "Default")
      (node (ref "18B") (pin "1") (pinfunction "P_1") (pintype "passive"))
      (node (ref "U6") (pin "P60") (pinfunction "IO_L13P_M1_2_P60") (pintype "bidirectional"))
    )
    (net (code "21") (name "A8'") (class "Default")
      (node (ref "U2") (pin "27") (pinfunction "A8_27") (pintype "input"))
      (node (ref "U3") (pin "39") (pinfunction "PE8_39") (pintype "bidirectional"))
      (node (ref "U6") (pin "P98") (pinfunction "IO_L34P_1_P98") (pintype "bidirectional"))
    )
    (net (code "22") (name "A9") (class "Default")
      (node (ref "17B") (pin "1") (pinfunction "P_1") (pintype "passive"))
      (node (ref "U6") (pin "P59") (pinfunction "IO_L13N_D10_2_P59") (pintype "bidirectional"))
    )
    (net (code "23") (name "A9'") (class "Default")
      (node (ref "U2") (pin "26") (pinfunction "A9_26") (pintype "input"))
      (node (ref "U3") (pin "40") (pinfunction "PE9_40") (pintype "bidirectional"))
      (node (ref "U6") (pin "P97") (pinfunction "IO_L34N_1_P97") (pintype "bidirectional"))
    )
    (net (code "24") (name "A10") (class "Default")
      (node (ref "16B") (pin "1") (pinfunction "P_1") (pintype "passive"))
      (node (ref "U6") (pin "P57") (pinfunction "IO_L14N_D12_2_P57") (pintype "bidirectional"))
    )
    (net (code "25") (name "A10'") (class "Default")
      (node (ref "U2") (pin "23") (pinfunction "A10_23") (pintype "input"))
      (node (ref "U3") (pin "41") (pinfunction "PE10_41") (pintype "bidirectional"))
      (node (ref "U6") (pin "P87") (pinfunction "IO_L42N_GCLK6_TRDY1_1_P87") (pintype "bidirectional"))
    )
    (net (code "26") (name "A11") (class "Default")
      (node (ref "15B") (pin "1") (pinfunction "P_1") (pintype "passive"))
      (node (ref "U6") (pin "P55") (pinfunction "IO_L30N_GCLK0_USERCCLK_2_P55") (pintype "bidirectional"))
    )
    (net (code "27") (name "A11'") (class "Default")
      (node (ref "U2") (pin "25") (pinfunction "A11_25") (pintype "input"))
      (node (ref "U3") (pin "42") (pinfunction "PE11_42") (pintype "bidirectional"))
      (node (ref "U6") (pin "P94") (pinfunction "IO_L40N_GCLK10_1_P94") (pintype "bidirectional"))
    )
    (net (code "28") (name "A12") (class "Default")
      (node (ref "14B") (pin "1") (pinfunction "P_1") (pintype "passive"))
      (node (ref "U6") (pin "P50") (pinfunction "IO_L31N_GCLK30_D15_2_P50") (pintype "bidirectional"))
    )
    (net (code "29") (name "A12'") (class "Default")
      (node (ref "U2") (pin "4") (pinfunction "A12_4") (pintype "input"))
      (node (ref "U3") (pin "43") (pinfunction "PE12_43") (pintype "bidirectional"))
      (node (ref "U6") (pin "P104") (pinfunction "IO_L1N_VREF_1_P104") (pintype "bidirectional"))
    )
    (net (code "30") (name "A13") (class "Default")
      (node (ref "13B") (pin "1") (pinfunction "P_1") (pintype "passive"))
      (node (ref "U6") (pin "P47") (pinfunction "IO_L48N_RDWR_B_VREF_2_P47") (pintype "bidirectional"))
    )
    (net (code "31") (name "A13'") (class "Default")
      (node (ref "U2") (pin "28") (pinfunction "A13_28") (pintype "input"))
      (node (ref "U3") (pin "44") (pinfunction "PE13_44") (pintype "bidirectional"))
      (node (ref "U6") (pin "P100") (pinfunction "IO_L33P_1_P100") (pintype "bidirectional"))
    )
    (net (code "32") (name "A14") (class "Default")
      (node (ref "12B") (pin "1") (pinfunction "P_1") (pintype "passive"))
      (node (ref "U6") (pin "P45") (pinfunction "IO_L49N_D4_2_P45") (pintype "bidirectional"))
    )
    (net (code "33") (name "A14'") (class "Default")
      (node (ref "U2") (pin "3") (pinfunction "A14_3") (pintype "input"))
      (node (ref "U3") (pin "45") (pinfunction "PE14_45") (pintype "bidirectional"))
      (node (ref "U6") (pin "P111") (pinfunction "IO_L66N_SCP0_0_P111") (pintype "bidirectional"))
    )
    (net (code "34") (name "A15") (class "Default")
      (node (ref "11B") (pin "1") (pinfunction "P_1") (pintype "passive"))
      (node (ref "U6") (pin "P43") (pinfunction "IO_L62N_D6_2_P43") (pintype "bidirectional"))
    )
    (net (code "35") (name "A15'") (class "Default")
      (node (ref "U2") (pin "31") (pinfunction "A15_31") (pintype "input"))
      (node (ref "U3") (pin "46") (pinfunction "PE15_46") (pintype "bidirectional"))
      (node (ref "U6") (pin "P112") (pinfunction "IO_L66P_SCP1_0_P112") (pintype "bidirectional"))
    )
    (net (code "36") (name "A16'") (class "Default")
      (node (ref "U2") (pin "2") (pinfunction "A16_2") (pintype "input"))
      (node (ref "U3") (pin "48") (pinfunction "PB11_48") (pintype "bidirectional"))
      (node (ref "U6") (pin "P114") (pinfunction "IO_L65N_SCP2_0_P114") (pintype "bidirectional"))
    )
    (net (code "37") (name "A17'") (class "Default")
      (node (ref "U2") (pin "30") (pinfunction "A17_30") (pintype "input"))
      (node (ref "U3") (pin "51") (pinfunction "PB12_51") (pintype "bidirectional"))
      (node (ref "U6") (pin "P61") (pinfunction "IO_L12N_D2_MISO3_2_P61") (pintype "bidirectional"))
    )
    (net (code "38") (name "A18'") (class "Default")
      (node (ref "U2") (pin "1") (pinfunction "A18_1") (pintype "input"))
      (node (ref "U3") (pin "52") (pinfunction "PB13_52") (pintype "bidirectional"))
      (node (ref "U6") (pin "P115") (pinfunction "IO_L65P_SCP3_0_P115") (pintype "bidirectional"))
    )
    (net (code "39") (name "B0") (class "Default")
      (node (ref "U3") (pin "55") (pinfunction "PD8_55") (pintype "bidirectional"))
      (node (ref "U6") (pin "P116") (pinfunction "IO_L64N_SCP4_0_P116") (pintype "bidirectional"))
    )
    (net (code "40") (name "B1") (class "Default")
      (node (ref "U3") (pin "56") (pinfunction "PD9_56") (pintype "bidirectional"))
      (node (ref "U6") (pin "P117") (pinfunction "IO_L64P_SCP5_0_P117") (pintype "bidirectional"))
    )
    (net (code "41") (name "B2") (class "Default")
      (node (ref "U3") (pin "57") (pinfunction "PD10_57") (pintype "bidirectional"))
      (node (ref "U6") (pin "P118") (pinfunction "IO_L63N_SCP6_0_P118") (pintype "bidirectional"))
    )
    (net (code "42") (name "B3") (class "Default")
      (node (ref "U3") (pin "58") (pinfunction "PD11_58") (pintype "bidirectional"))
      (node (ref "U6") (pin "P119") (pinfunction "IO_L63P_SCP7_0_P119") (pintype "bidirectional"))
    )
    (net (code "43") (name "B4") (class "Default")
      (node (ref "U3") (pin "59") (pinfunction "PD12_59") (pintype "bidirectional"))
      (node (ref "U6") (pin "P120") (pinfunction "IO_L62N_VREF_0_P120") (pintype "bidirectional"))
    )
    (net (code "44") (name "B5") (class "Default")
      (node (ref "U3") (pin "60") (pinfunction "PD13_60") (pintype "bidirectional"))
      (node (ref "U6") (pin "P121") (pinfunction "IO_L62P_0_P121") (pintype "bidirectional"))
    )
    (net (code "45") (name "B6") (class "Default")
      (node (ref "U3") (pin "61") (pinfunction "PD14_61") (pintype "bidirectional"))
      (node (ref "U6") (pin "P123") (pinfunction "IO_L37N_GCLK12_0_P123") (pintype "bidirectional"))
    )
    (net (code "46") (name "B7") (class "Default")
      (node (ref "U3") (pin "62") (pinfunction "PD15_62") (pintype "bidirectional"))
      (node (ref "U6") (pin "P124") (pinfunction "IO_L37P_GCLK13_0_P124") (pintype "bidirectional"))
    )
    (net (code "47") (name "BOOT0") (class "Default")
      (node (ref "R24") (pin "1") (pinfunction "1_1") (pintype "passive"))
      (node (ref "R30") (pin "2") (pinfunction "2_2") (pintype "passive"))
      (node (ref "U3") (pin "94") (pinfunction "BOOT0_94") (pintype "bidirectional"))
    )
    (net (code "48") (name "BRIGHT") (class "Default")
      (node (ref "R33") (pin "1") (pinfunction "1_1") (pintype "passive"))
      (node (ref "R34") (pin "1") (pinfunction "1_1") (pintype "passive"))
      (node (ref "R35") (pin "1") (pinfunction "1_1") (pintype "passive"))
      (node (ref "U6") (pin "P11") (pinfunction "IO_L49N_3_P11") (pintype "bidirectional"))
    )
    (net (code "49") (name "CC1") (class "Default")
      (node (ref "J3") (pin "A5") (pinfunction "CC1_A5") (pintype "bidirectional"))
    )
    (net (code "50") (name "CC2") (class "Default")
      (node (ref "J3") (pin "B5") (pinfunction "CC2_B5") (pintype "bidirectional"))
    )
    (net (code "51") (name "CFG_CLK") (class "Default")
      (node (ref "U3") (pin "35") (pinfunction "PB0_35") (pintype "bidirectional"))
      (node (ref "U6") (pin "P17") (pinfunction "IO_L43P_GCLK23_3_P17") (pintype "bidirectional"))
    )
    (net (code "52") (name "CFG_DATA") (class "Default")
      (node (ref "U3") (pin "89") (pinfunction "PB3_89") (pintype "bidirectional"))
      (node (ref "U6") (pin "P15") (pinfunction "IO_L44P_GCLK21_3_P15") (pintype "bidirectional"))
    )
    (net (code "53") (name "CFG_RESET") (class "Default")
      (node (ref "U3") (pin "36") (pinfunction "PB1_36") (pintype "bidirectional"))
      (node (ref "U6") (pin "P16") (pinfunction "IO_L43N_GCLK22_IRDY2_3_P16") (pintype "bidirectional"))
    )
    (net (code "54") (name "COMPOSITE") (class "Default")
      (node (ref "R4") (pin "1") (pinfunction "1_1") (pintype "passive"))
      (node (ref "X1") (pin "20") (pinfunction "20_20") (pintype "passive"))
      (node (ref "X2") (pin "2") (pinfunction "1_2") (pintype "passive"))
    )
    (net (code "55") (name "CSYNC") (class "Default")
      (node (ref "SJ1") (pin "1") (pinfunction "1_1") (pintype "passive"))
      (node (ref "U1") (pin "16") (pinfunction "HSYNC_16") (pintype "input"))
      (node (ref "U6") (pin "P10") (pinfunction "IO_L50P_3_P10") (pintype "bidirectional"))
    )
    (net (code "56") (name "CS_LLS") (class "Default")
      (node (ref "MICRO_SD1") (pin "2") (pinfunction "CD/DAT3_2") (pintype "bidirectional"))
      (node (ref "R21") (pin "2") (pinfunction "2_2") (pintype "passive"))
    )
    (net (code "57") (name "CTRL_CLK") (class "Default")
      (node (ref "U3") (pin "90") (pinfunction "PB4_90") (pintype "bidirectional"))
      (node (ref "U6") (pin "P6") (pinfunction "IO_L52P_3_P6") (pintype "bidirectional"))
    )
    (net (code "58") (name "D0") (class "Default")
      (node (ref "4A") (pin "1") (pinfunction "P_1") (pintype "passive"))
      (node (ref "U2") (pin "13") (pinfunction "DQ0_13") (pintype "output"))
      (node (ref "U6") (pin "P23") (pinfunction "IO_L41N_GCLK26_3_P23") (pintype "bidirectional"))
    )
    (net (code "59") (name "D1") (class "Default")
      (node (ref "5A") (pin "1") (pinfunction "P_1") (pintype "passive"))
      (node (ref "U2") (pin "14") (pinfunction "DQ1_14") (pintype "output"))
      (node (ref "U6") (pin "P26") (pinfunction "IO_L37N_3_P26") (pintype "bidirectional"))
    )
    (net (code "60") (name "D2") (class "Default")
      (node (ref "6A") (pin "1") (pinfunction "P_1") (pintype "passive"))
      (node (ref "U2") (pin "15") (pinfunction "DQ2_15") (pintype "output"))
      (node (ref "U6") (pin "P27") (pinfunction "IO_L37P_3_P27") (pintype "bidirectional"))
    )
    (net (code "61") (name "D3") (class "Default")
      (node (ref "9A") (pin "1") (pinfunction "P_1") (pintype "passive"))
      (node (ref "U2") (pin "17") (pinfunction "DQ3_17") (pintype "output"))
      (node (ref "U6") (pin "P34") (pinfunction "IO_L1N_VREF_3_P34") (pintype "bidirectional"))
    )
    (net (code "62") (name "D4") (class "Default")
      (node (ref "10A") (pin "1") (pinfunction "P_1") (pintype "passive"))
      (node (ref "U2") (pin "18") (pinfunction "DQ4_18") (pintype "output"))
      (node (ref "U6") (pin "P39") (pinfunction "IO_L65P_INIT_B_2_P39") (pintype "bidirectional"))
    )
    (net (code "63") (name "D5") (class "Default")
      (node (ref "8A") (pin "1") (pinfunction "P_1") (pintype "passive"))
      (node (ref "U2") (pin "19") (pinfunction "DQ5_19") (pintype "output"))
      (node (ref "U6") (pin "P32") (pinfunction "IO_L2N_3_P32") (pintype "bidirectional"))
    )
    (net (code "64") (name "D6") (class "Default")
      (node (ref "7A") (pin "1") (pinfunction "P_1") (pintype "passive"))
      (node (ref "U2") (pin "20") (pinfunction "DQ6_20") (pintype "output"))
      (node (ref "U6") (pin "P29") (pinfunction "IO_L36N_3_P29") (pintype "bidirectional"))
    )
    (net (code "65") (name "D7") (class "Default")
      (node (ref "1A") (pin "1") (pinfunction "P_1") (pintype "passive"))
      (node (ref "U2") (pin "21") (pinfunction "DQ7_21") (pintype "output"))
      (node (ref "U6") (pin "P21") (pinfunction "IO_L42N_GCLK24_3_P21") (pintype "bidirectional"))
    )
    (net (code "66") (name "DI_LLS") (class "Default")
      (node (ref "MICRO_SD1") (pin "3") (pinfunction "CMD_3") (pintype "bidirectional"))
      (node (ref "R17") (pin "2") (pinfunction "2_2") (pintype "passive"))
    )
    (net (code "67") (name "DOWN") (class "Default")
      (node (ref "J2") (pin "2") (pinfunction "2_2") (pintype "passive"))
      (node (ref "U6") (pin "P79") (pinfunction "IO_L47P_1_P79") (pintype "bidirectional"))
    )
    (net (code "68") (name "EN_M1_NOT") (class "Default")
      (node (ref "U3") (pin "25") (pinfunction "PA2_25") (pintype "bidirectional"))
      (node (ref "U6") (pin "P140") (pinfunction "IO_L3P_0_P140") (pintype "bidirectional"))
    )
    (net (code "69") (name "FIRE") (class "Default")
      (node (ref "J2") (pin "6") (pinfunction "6_6") (pintype "passive"))
      (node (ref "U6") (pin "P82") (pinfunction "IO_L45N_1_P82") (pintype "bidirectional"))
    )
    (net (code "70") (name "FLASH_CS") (class "Default")
      (node (ref "U4") (pin "1") (pinfunction "CS_1") (pintype "bidirectional"))
      (node (ref "U6") (pin "P38") (pinfunction "IO_L65N_CSO_B_2_P38") (pintype "bidirectional"))
    )
    (net (code "71") (name "FLASH_MISO") (class "Default")
      (node (ref "U4") (pin "2") (pinfunction "MISO_2") (pintype "bidirectional"))
      (node (ref "U6") (pin "P65") (pinfunction "IO_L3P_D0_DIN_MISO_MISO1_2_P65") (pintype "bidirectional"))
    )
    (net (code "72") (name "FLASH_MOSI") (class "Default")
      (node (ref "U4") (pin "5") (pinfunction "MOSI_5") (pintype "bidirectional"))
      (node (ref "U6") (pin "P64") (pinfunction "IO_L3N_MOSI_CSI_B_MISO0_2_P64") (pintype "bidirectional"))
    )
    (net (code "73") (name "FLASH_SCLK") (class "Default")
      (node (ref "U4") (pin "6") (pinfunction "SCK_6") (pintype "bidirectional"))
      (node (ref "U6") (pin "P70") (pinfunction "IO_L1P_CCLK_2_P70") (pintype "bidirectional"))
    )
    (net (code "74") (name "GET_CTRL_REG") (class "Default")
      (node (ref "U3") (pin "66") (pinfunction "PC9_66") (pintype "bidirectional"))
      (node (ref "U6") (pin "P5") (pinfunction "IO_L52N_3_P5") (pintype "bidirectional"))
    )
    (net (code "75") (name "GET_DATA_REG") (class "Default")
      (node (ref "U3") (pin "78") (pinfunction "PC10_78") (pintype "bidirectional"))
      (node (ref "U6") (pin "P2") (pinfunction "IO_L83P_3_P2") (pintype "bidirectional"))
    )
    (net (code "76") (name "GND") (class "Default")
      (node (ref "4B") (pin "1") (pinfunction "P_1") (pintype "passive"))
      (node (ref "5B") (pin "1") (pinfunction "P_1") (pintype "passive"))
      (node (ref "BT1") (pin "N") (pinfunction "NEG_N") (pintype "passive"))
      (node (ref "C10") (pin "2") (pinfunction "2_2") (pintype "passive"))
      (node (ref "C11") (pin "1") (pinfunction "1_1") (pintype "passive"))
      (node (ref "C12") (pin "1") (pinfunction "1_1") (pintype "passive"))
      (node (ref "C18") (pin "2") (pinfunction "2_2") (pintype "passive"))
      (node (ref "C19") (pin "2") (pinfunction "2_2") (pintype "passive"))
      (node (ref "C2") (pin "2") (pinfunction "2_2") (pintype "passive"))
      (node (ref "C22") (pin "1") (pinfunction "1_1") (pintype "passive"))
      (node (ref "C23") (pin "1") (pinfunction "1_1") (pintype "passive"))
      (node (ref "C24") (pin "2") (pinfunction "2_2") (pintype "passive"))
      (node (ref "C25") (pin "2") (pinfunction "2_2") (pintype "passive"))
      (node (ref "C26") (pin "2") (pinfunction "2_2") (pintype "passive"))
      (node (ref "C3") (pin "2") (pinfunction "2_2") (pintype "passive"))
      (node (ref "C33") (pin "2") (pinfunction "2_2") (pintype "passive"))
      (node (ref "C4") (pin "1") (pinfunction "1_1") (pintype "passive"))
      (node (ref "C5") (pin "1") (pinfunction "1_1") (pintype "passive"))
      (node (ref "C6") (pin "2") (pinfunction "2_2") (pintype "passive"))
      (node (ref "C7") (pin "2") (pinfunction "2_2") (pintype "passive"))
      (node (ref "C8") (pin "1") (pinfunction "1_1") (pintype "passive"))
      (node (ref "C9") (pin "1") (pinfunction "1_1") (pintype "passive"))
      (node (ref "IC2") (pin "1") (pinfunction "GND_1") (pintype "power_in"))
      (node (ref "IC5") (pin "1") (pinfunction "GND_1") (pintype "power_in"))
      (node (ref "J2") (pin "8") (pinfunction "8_8") (pintype "passive"))
      (node (ref "J3") (pin "A1_B12") (pinfunction "GND_A1_B12") (pintype "power_in"))
      (node (ref "J3") (pin "B1_A12") (pinfunction "GND_B1_A12") (pintype "power_in"))
      (node (ref "J3") (pin "SH1") (pinfunction "SHIELD_SH1") (pintype "passive"))
      (node (ref "J3") (pin "SH2") (pinfunction "SHIELD_SH2") (pintype "passive"))
      (node (ref "J3") (pin "SH3") (pinfunction "SHIELD_SH3") (pintype "passive"))
      (node (ref "J3") (pin "SH4") (pinfunction "SHIELD_SH4") (pintype "passive"))
      (node (ref "J4") (pin "1") (pinfunction "1_1") (pintype "passive"))
      (node (ref "JP4") (pin "2") (pinfunction "2_2") (pintype "passive"))
      (node (ref "JP5") (pin "2") (pinfunction "2_2") (pintype "passive"))
      (node (ref "JP6") (pin "2") (pinfunction "2_2") (pintype "passive"))
      (node (ref "JP8") (pin "2") (pinfunction "2_2") (pintype "passive"))
      (node (ref "LED3") (pin "P1") (pinfunction "C_P1") (pintype "passive"))
      (node (ref "LED3") (pin "P2") (pinfunction "C_P2") (pintype "passive"))
      (node (ref "LED3") (pin "P3") (pinfunction "C_P3") (pintype "passive"))
      (node (ref "MICRO_SD1") (pin "6") (pinfunction "VSS_6") (pintype "power_in"))
      (node (ref "MICRO_SD1") (pin "MP1") (pinfunction "SHIELD_MP1") (pintype "power_in"))
      (node (ref "MICRO_SD1") (pin "MP2") (pinfunction "SHIELD_MP2") (pintype "power_in"))
      (node (ref "MICRO_SD1") (pin "MP3") (pinfunction "SHIELD_MP3") (pintype "power_in"))
      (node (ref "MICRO_SD1") (pin "MP4") (pinfunction "SHIELD_MP4") (pintype "power_in"))
      (node (ref "R19") (pin "2") (pinfunction "2_2") (pintype "passive"))
      (node (ref "R25") (pin "1") (pinfunction "1_1") (pintype "passive"))
      (node (ref "R27") (pin "2") (pinfunction "2_2") (pintype "passive"))
      (node (ref "R28") (pin "2") (pinfunction "2_2") (pintype "passive"))
      (node (ref "R30") (pin "1") (pinfunction "1_1") (pintype "passive"))
      (node (ref "R37") (pin "2") (pinfunction "2_2") (pintype "passive"))
      (node (ref "S1") (pin "1") (pinfunction "P_1") (pintype "passive"))
      (node (ref "U1") (pin "12") (pinfunction "SELECT_12") (pintype "input"))
      (node (ref "U1") (pin "13") (pinfunction "DGND_13") (pintype "passive"))
      (node (ref "U1") (pin "2") (pinfunction "AGND_2") (pintype "passive"))
      (node (ref "U2") (pin "16") (pinfunction "VSS_16") (pintype "output"))
      (node (ref "U2") (pin "22") (pinfunction "CE_22") (pintype "input"))
      (node (ref "U3") (pin "10") (pinfunction "VSS_10") (pintype "bidirectional"))
      (node (ref "U3") (pin "20") (pinfunction "VSSA_20") (pintype "bidirectional"))
      (node (ref "U3") (pin "27") (pinfunction "VSS_27") (pintype "bidirectional"))
      (node (ref "U3") (pin "74") (pinfunction "VSS_74") (pintype "bidirectional"))
      (node (ref "U3") (pin "99") (pinfunction "VSS_99") (pintype "bidirectional"))
      (node (ref "U4") (pin "4") (pinfunction "GND_4") (pintype "power_in"))
      (node (ref "U5") (pin "7") (pinfunction "GND_7") (pintype "power_in"))
      (node (ref "U6") (pin "P108") (pinfunction "GND_P108") (pintype "bidirectional"))
      (node (ref "U6") (pin "P113") (pinfunction "GND_P113") (pintype "bidirectional"))
      (node (ref "U6") (pin "P13") (pinfunction "GND_P13") (pintype "bidirectional"))
      (node (ref "U6") (pin "P130") (pinfunction "GND_P130") (pintype "bidirectional"))
      (node (ref "U6") (pin "P136") (pinfunction "GND_P136") (pintype "bidirectional"))
      (node (ref "U6") (pin "P25") (pinfunction "GND_P25") (pintype "bidirectional"))
      (node (ref "U6") (pin "P3") (pinfunction "GND_P3") (pintype "bidirectional"))
      (node (ref "U6") (pin "P49") (pinfunction "GND_P49") (pintype "bidirectional"))
      (node (ref "U6") (pin "P54") (pinfunction "GND_P54") (pintype "bidirectional"))
      (node (ref "U6") (pin "P68") (pinfunction "GND_P68") (pintype "bidirectional"))
      (node (ref "U6") (pin "P73") (pinfunction "SUSPEND_P73") (pintype "bidirectional"))
      (node (ref "U6") (pin "P77") (pinfunction "GND_P77") (pintype "bidirectional"))
      (node (ref "U6") (pin "P91") (pinfunction "GND_P91") (pintype "bidirectional"))
      (node (ref "U6") (pin "P96") (pinfunction "GND_P96") (pintype "bidirectional"))
      (node (ref "X1") (pin "13") (pinfunction "13_13") (pintype "passive"))
      (node (ref "X1") (pin "14") (pinfunction "14_14") (pintype "passive"))
      (node (ref "X1") (pin "17") (pinfunction "17_17") (pintype "passive"))
      (node (ref "X1") (pin "18") (pinfunction "18_18") (pintype "passive"))
      (node (ref "X1") (pin "21") (pinfunction "21_21") (pintype "passive"))
      (node (ref "X1") (pin "4") (pinfunction "4_4") (pintype "passive"))
      (node (ref "X1") (pin "5") (pinfunction "5_5") (pintype "passive"))
      (node (ref "X1") (pin "8") (pinfunction "8_8") (pintype "passive"))
      (node (ref "X1") (pin "9") (pinfunction "9_9") (pintype "passive"))
      (node (ref "X2") (pin "1") (pinfunction "2_1") (pintype "passive"))
    )
    (net (code "77") (name "LEDB") (class "Default")
      (node (ref "R3") (pin "1") (pinfunction "1_1") (pintype "passive"))
      (node (ref "U3") (pin "64") (pinfunction "PC7_64") (pintype "bidirectional"))
    )
    (net (code "78") (name "LEDG") (class "Default")
      (node (ref "R13") (pin "1") (pinfunction "1_1") (pintype "passive"))
      (node (ref "U3") (pin "63") (pinfunction "PC6_63") (pintype "bidirectional"))
    )
    (net (code "79") (name "LEDR") (class "Default")
      (node (ref "R2") (pin "1") (pinfunction "1_1") (pintype "passive"))
      (node (ref "U3") (pin "65") (pinfunction "PC8_65") (pintype "bidirectional"))
    )
    (net (code "80") (name "LEFT") (class "Default")
      (node (ref "J2") (pin "3") (pinfunction "3_3") (pintype "passive"))
      (node (ref "U6") (pin "P80") (pinfunction "IO_L46N_1_P80") (pintype "bidirectional"))
    )
    (net (code "81") (name "LE_IL") (class "Default")
      (node (ref "U3") (pin "7") (pinfunction "PC13_7") (pintype "bidirectional"))
      (node (ref "U6") (pin "P14") (pinfunction "IO_L44N_GCLK20_3_P14") (pintype "bidirectional"))
    )
    (net (code "82") (name "MISO") (class "Default")
      (node (ref "R20") (pin "1") (pinfunction "1_1") (pintype "passive"))
      (node (ref "U3") (pin "31") (pinfunction "PA6_31") (pintype "bidirectional"))
    )
    (net (code "83") (name "MOSI") (class "Default")
      (node (ref "R17") (pin "1") (pinfunction "1_1") (pintype "passive"))
      (node (ref "U3") (pin "32") (pinfunction "PA7_32") (pintype "bidirectional"))
    )
    (net (code "84") (name "Net-(1B-P)") (class "Default")
      (node (ref "1B") (pin "1") (pinfunction "P_1") (pintype "passive"))
      (node (ref "D4") (pin "A") (pinfunction "A_A") (pintype "passive"))
    )
    (net (code "85") (name "Net-(BT1-POS)") (class "Default")
      (node (ref "BT1") (pin "P") (pinfunction "POS_P") (pintype "passive"))
      (node (ref "D3") (pin "2") (pinfunction "A2_2") (pintype "passive"))
      (node (ref "U3") (pin "16") (pinfunction "PC1_16") (pintype "bidirectional"))
    )
    (net (code "86") (name "Net-(C1-Pad-)") (class "Default")
      (node (ref "C1") (pin "-") (pinfunction "-_-") (pintype "passive"))
      (node (ref "R4") (pin "2") (pinfunction "2_2") (pintype "passive"))
    )
    (net (code "87") (name "Net-(C9-Pad2)") (class "Default")
      (node (ref "C9") (pin "2") (pinfunction "2_2") (pintype "passive"))
      (node (ref "R5") (pin "2") (pinfunction "2_2") (pintype "passive"))
    )
    (net (code "88") (name "Net-(C13-Pad1)") (class "Default")
      (node (ref "C13") (pin "1") (pinfunction "1_1") (pintype "passive"))
      (node (ref "J4") (pin "4") (pinfunction "4_4") (pintype "passive"))
      (node (ref "J4") (pin "5") (pinfunction "5_5") (pintype "passive"))
    )
    (net (code "89") (name "Net-(C13-Pad2)") (class "Default")
      (node (ref "C13") (pin "2") (pinfunction "2_2") (pintype "passive"))
      (node (ref "R6") (pin "2") (pinfunction "2_2") (pintype "passive"))
    )
    (net (code "90") (name "Net-(C14-Pad-)") (class "Default")
      (node (ref "C14") (pin "-") (pinfunction "-_-") (pintype "passive"))
      (node (ref "JP1") (pin "2") (pinfunction "2_2") (pintype "passive"))
    )
    (net (code "91") (name "Net-(D3-CC)") (class "Default")
      (node (ref "D3") (pin "3") (pinfunction "CC_3") (pintype "passive"))
      (node (ref "U3") (pin "6") (pinfunction "VBAT_6") (pintype "bidirectional"))
    )
    (net (code "92") (name "Net-(J3-DN1)") (class "Default")
      (node (ref "J3") (pin "A7") (pinfunction "DN1_A7") (pintype "bidirectional"))
      (node (ref "J3") (pin "B7") (pinfunction "DN2_B7") (pintype "bidirectional"))
      (node (ref "R26") (pin "1") (pinfunction "1_1") (pintype "passive"))
    )
    (net (code "93") (name "Net-(J3-DP1)") (class "Default")
      (node (ref "J3") (pin "A6") (pinfunction "DP1_A6") (pintype "bidirectional"))
      (node (ref "J3") (pin "B6") (pinfunction "DP2_B6") (pintype "bidirectional"))
      (node (ref "R22") (pin "1") (pinfunction "1_1") (pintype "passive"))
      (node (ref "R23") (pin "1") (pinfunction "1_1") (pintype "passive"))
    )
    (net (code "94") (name "Net-(JP2-Pad1)") (class "Default")
      (node (ref "JP2") (pin "1") (pinfunction "1_1") (pintype "passive"))
      (node (ref "X1") (pin "16") (pinfunction "16_16") (pintype "passive"))
    )
    (net (code "95") (name "Net-(JP2-Pad2)") (class "Default")
      (node (ref "JP2") (pin "2") (pinfunction "2_2") (pintype "passive"))
      (node (ref "R36") (pin "1") (pinfunction "1_1") (pintype "passive"))
    )
    (net (code "96") (name "Net-(JP7-Pad1)") (class "Default")
      (node (ref "JP7") (pin "1") (pinfunction "1_1") (pintype "passive"))
      (node (ref "R24") (pin "2") (pinfunction "2_2") (pintype "passive"))
    )
    (net (code "97") (name "Net-(JP7-Pad3)") (class "Default")
      (node (ref "JP7") (pin "3") (pinfunction "3_3") (pintype "passive"))
      (node (ref "R16") (pin "1") (pinfunction "1_1") (pintype "passive"))
    )
    (net (code "98") (name "Net-(LED2-PadA)") (class "Default")
      (node (ref "LED2") (pin "A") (pinfunction "A_A") (pintype "passive"))
      (node (ref "R11") (pin "2") (pinfunction "2_2") (pintype "passive"))
    )
    (net (code "99") (name "Net-(LED3A-A)") (class "Default")
      (node (ref "LED3") (pin "P6") (pinfunction "A_P6") (pintype "passive"))
      (node (ref "R3") (pin "2") (pinfunction "2_2") (pintype "passive"))
    )
    (net (code "100") (name "Net-(LED3B-A)") (class "Default")
      (node (ref "LED3") (pin "P5") (pinfunction "A_P5") (pintype "passive"))
      (node (ref "R13") (pin "2") (pinfunction "2_2") (pintype "passive"))
    )
    (net (code "101") (name "Net-(LED3C-A)") (class "Default")
      (node (ref "LED3") (pin "P4") (pinfunction "A_P4") (pintype "passive"))
      (node (ref "R2") (pin "2") (pinfunction "2_2") (pintype "passive"))
    )
    (net (code "102") (name "Net-(MICRO_SD1-DAT0)") (class "Default")
      (node (ref "MICRO_SD1") (pin "7") (pinfunction "DAT0_7") (pintype "bidirectional"))
      (node (ref "R20") (pin "2") (pinfunction "2_2") (pintype "passive"))
    )
    (net (code "103") (name "Net-(Q3-2)") (class "Default")
      (node (ref "C12") (pin "2") (pinfunction "2_2") (pintype "passive"))
      (node (ref "Q3") (pin "3") (pinfunction "2_3") (pintype "passive"))
      (node (ref "R14") (pin "2") (pinfunction "2_2") (pintype "passive"))
      (node (ref "U3") (pin "13") (pinfunction "PH1_13") (pintype "bidirectional"))
    )
    (net (code "104") (name "Net-(R10-Pad2)") (class "Default")
      (node (ref "R10") (pin "2") (pinfunction "2_2") (pintype "passive"))
      (node (ref "R32") (pin "2") (pinfunction "2_2") (pintype "passive"))
      (node (ref "R35") (pin "2") (pinfunction "2_2") (pintype "passive"))
    )
    (net (code "105") (name "Net-(R29-Pad2)") (class "Default")
      (node (ref "R29") (pin "2") (pinfunction "2_2") (pintype "passive"))
      (node (ref "R33") (pin "2") (pinfunction "2_2") (pintype "passive"))
      (node (ref "R8") (pin "2") (pinfunction "2_2") (pintype "passive"))
    )
    (net (code "106") (name "Net-(R31-Pad2)") (class "Default")
      (node (ref "R31") (pin "2") (pinfunction "2_2") (pintype "passive"))
      (node (ref "R34") (pin "2") (pinfunction "2_2") (pintype "passive"))
      (node (ref "R9") (pin "2") (pinfunction "2_2") (pintype "passive"))
    )
    (net (code "107") (name "Net-(U1-COMP)") (class "Default")
      (node (ref "C1") (pin "+") (pinfunction "+_+") (pintype "passive"))
      (node (ref "SJ1") (pin "2") (pinfunction "2_2") (pintype "passive"))
      (node (ref "U1") (pin "10") (pinfunction "COMP_10") (pintype "output"))
    )
    (net (code "108") (name "Net-(U3-PC14)") (class "Default")
      (node (ref "C22") (pin "2") (pinfunction "2_2") (pintype "passive"))
      (node (ref "Q4") (pin "2") (pinfunction "2_2") (pintype "passive"))
      (node (ref "U3") (pin "8") (pinfunction "PC14_8") (pintype "bidirectional"))
    )
    (net (code "109") (name "Net-(U3-PC15)") (class "Default")
      (node (ref "C23") (pin "2") (pinfunction "2_2") (pintype "passive"))
      (node (ref "Q4") (pin "1") (pinfunction "1_1") (pintype "passive"))
      (node (ref "U3") (pin "9") (pinfunction "PC15_9") (pintype "bidirectional"))
    )
    (net (code "110") (name "Net-(U3-PH0)") (class "Default")
      (node (ref "C11") (pin "2") (pinfunction "2_2") (pintype "passive"))
      (node (ref "Q3") (pin "1") (pinfunction "1_1") (pintype "passive"))
      (node (ref "R14") (pin "1") (pinfunction "1_1") (pintype "passive"))
      (node (ref "U3") (pin "12") (pinfunction "PH0_12") (pintype "bidirectional"))
    )
    (net (code "111") (name "Net-(U3-VCAP_1)") (class "Default")
      (node (ref "C10") (pin "1") (pinfunction "1_1") (pintype "passive"))
      (node (ref "U3") (pin "49") (pinfunction "VCAP_1_49") (pintype "bidirectional"))
    )
    (net (code "112") (name "Net-(U3-VCAP_2)") (class "Default")
      (node (ref "C7") (pin "1") (pinfunction "1_1") (pintype "passive"))
      (node (ref "U3") (pin "73") (pinfunction "VCAP_2_73") (pintype "bidirectional"))
    )
    (net (code "113") (name "Net-(U5-IN+)") (class "Default")
      (node (ref "R6") (pin "1") (pinfunction "1_1") (pintype "passive"))
      (node (ref "U5") (pin "3") (pinfunction "IN+_3") (pintype "input"))
    )
    (net (code "114") (name "Net-(U5-IN-)") (class "Default")
      (node (ref "R5") (pin "1") (pinfunction "1_1") (pintype "passive"))
      (node (ref "U5") (pin "4") (pinfunction "IN-_4") (pintype "input"))
    )
    (net (code "115") (name "Net-(U5-VO+)") (class "Default")
      (node (ref "C14") (pin "+") (pinfunction "+_+") (pintype "passive"))
      (node (ref "U5") (pin "5") (pinfunction "VO+_5") (pintype "output"))
    )
    (net (code "116") (name "Net-(U5-VO-)") (class "Default")
      (node (ref "JP1") (pin "1") (pinfunction "1_1") (pintype "passive"))
      (node (ref "U5") (pin "8") (pinfunction "VO-_8") (pintype "output"))
    )
    (net (code "117") (name "Net-(U5-~{SD})") (class "Default")
      (node (ref "R7") (pin "1") (pinfunction "1_1") (pintype "passive"))
      (node (ref "U5") (pin "1") (pinfunction "~{SD}_1") (pintype "input"))
    )
    (net (code "118") (name "Net-(U6-PROGRAM_B_2)") (class "Default")
      (node (ref "R12") (pin "2") (pinfunction "2_2") (pintype "passive"))
      (node (ref "U6") (pin "P37") (pinfunction "PROGRAM_B_2_P37") (pintype "bidirectional"))
    )
    (net (code "119") (name "O0") (class "Default")
      (node (ref "U3") (pin "81") (pinfunction "PD0_81") (pintype "bidirectional"))
      (node (ref "U6") (pin "P126") (pinfunction "IO_L36N_GCLK14_0_P126") (pintype "bidirectional"))
    )
    (net (code "120") (name "O1") (class "Default")
      (node (ref "U3") (pin "82") (pinfunction "PD1_82") (pintype "bidirectional"))
      (node (ref "U6") (pin "P127") (pinfunction "IO_L36P_GCLK15_0_P127") (pintype "bidirectional"))
    )
    (net (code "121") (name "O2") (class "Default")
      (node (ref "U3") (pin "83") (pinfunction "PD2_83") (pintype "bidirectional"))
      (node (ref "U6") (pin "P131") (pinfunction "IO_L35N_GCLK16_0_P131") (pintype "bidirectional"))
    )
    (net (code "122") (name "O3") (class "Default")
      (node (ref "U3") (pin "84") (pinfunction "PD3_84") (pintype "bidirectional"))
      (node (ref "U6") (pin "P132") (pinfunction "IO_L35P_GCLK17_0_P132") (pintype "bidirectional"))
    )
    (net (code "123") (name "O4") (class "Default")
      (node (ref "U3") (pin "85") (pinfunction "PD4_85") (pintype "bidirectional"))
      (node (ref "U6") (pin "P133") (pinfunction "IO_L34N_GCLK18_0_P133") (pintype "bidirectional"))
    )
    (net (code "124") (name "O5") (class "Default")
      (node (ref "U3") (pin "86") (pinfunction "PD5_86") (pintype "bidirectional"))
      (node (ref "U6") (pin "P134") (pinfunction "IO_L34P_GCLK19_0_P134") (pintype "bidirectional"))
    )
    (net (code "125") (name "O6") (class "Default")
      (node (ref "U3") (pin "87") (pinfunction "PD6_87") (pintype "bidirectional"))
      (node (ref "U6") (pin "P137") (pinfunction "IO_L4N_0_P137") (pintype "bidirectional"))
    )
    (net (code "126") (name "O7") (class "Default")
      (node (ref "U3") (pin "88") (pinfunction "PD7_88") (pintype "bidirectional"))
      (node (ref "U6") (pin "P138") (pinfunction "IO_L4P_0_P138") (pintype "bidirectional"))
    )
    (net (code "127") (name "PA11{slash}USB_DN") (class "Default")
      (node (ref "R26") (pin "2") (pinfunction "2_2") (pintype "passive"))
      (node (ref "U3") (pin "70") (pinfunction "PA11_70") (pintype "bidirectional"))
    )
    (net (code "128") (name "PA12{slash}USB_DP") (class "Default")
      (node (ref "R23") (pin "2") (pinfunction "2_2") (pintype "passive"))
      (node (ref "U3") (pin "71") (pinfunction "PA12_71") (pintype "bidirectional"))
    )
    (net (code "129") (name "PA13{slash}JTMS{slash}SWDIO") (class "Default")
      (node (ref "JP8") (pin "1") (pinfunction "1_1") (pintype "passive"))
      (node (ref "U3") (pin "72") (pinfunction "PA13_72") (pintype "bidirectional"))
    )
    (net (code "130") (name "PA14{slash}JTCK{slash}SWCLK") (class "Default")
      (node (ref "JP8") (pin "3") (pinfunction "3_3") (pintype "passive"))
      (node (ref "U3") (pin "76") (pinfunction "PA14_76") (pintype "bidirectional"))
    )
    (net (code "131") (name "PAGE_A8") (class "Default")
      (node (ref "U3") (pin "24") (pinfunction "PA1_24") (pintype "bidirectional"))
      (node (ref "U6") (pin "P143") (pinfunction "IO_L1N_VREF_0_P143") (pintype "bidirectional"))
    )
    (net (code "132") (name "PAL-NTSC") (class "Default")
      (node (ref "U1") (pin "1") (pinfunction "STND_1") (pintype "input"))
      (node (ref "U6") (pin "P22") (pinfunction "IO_L42P_GCLK25_TRDY2_3_P22") (pintype "bidirectional"))
    )
    (net (code "133") (name "PB2{slash}BOOT1") (class "Default")
      (node (ref "R16") (pin "2") (pinfunction "2_2") (pintype "passive"))
      (node (ref "R25") (pin "2") (pinfunction "2_2") (pintype "passive"))
      (node (ref "U3") (pin "37") (pinfunction "PB2_37") (pintype "bidirectional"))
    )
    (net (code "134") (name "PS2_CLOCK") (class "Default")
      (node (ref "JP6") (pin "3") (pinfunction "3_3") (pintype "passive"))
      (node (ref "U3") (pin "80") (pinfunction "PC12_80") (pintype "bidirectional"))
    )
    (net (code "135") (name "PS2_DATA") (class "Default")
      (node (ref "JP6") (pin "4") (pinfunction "4_4") (pintype "passive"))
      (node (ref "U3") (pin "79") (pinfunction "PC11_79") (pintype "bidirectional"))
    )
    (net (code "136") (name "RESET") (class "Default")
      (node (ref "C5") (pin "2") (pinfunction "2_2") (pintype "passive"))
      (node (ref "D1") (pin "A") (pinfunction "A_A") (pintype "passive"))
      (node (ref "R15") (pin "1") (pinfunction "1_1") (pintype "passive"))
      (node (ref "S1") (pin "2") (pinfunction "S_2") (pintype "passive"))
      (node (ref "U3") (pin "14") (pinfunction "NRST_14") (pintype "bidirectional"))
    )
    (net (code "137") (name "RIGHT") (class "Default")
      (node (ref "J2") (pin "4") (pinfunction "4_4") (pintype "passive"))
      (node (ref "U6") (pin "P81") (pinfunction "IO_L46P_1_P81") (pintype "bidirectional"))
    )
    (net (code "138") (name "ROM_WR_EN") (class "Default")
      (node (ref "U3") (pin "67") (pinfunction "PA8_67") (pintype "bidirectional"))
      (node (ref "U6") (pin "P142") (pinfunction "IO_L2P_0_P142") (pintype "bidirectional"))
    )
    (net (code "139") (name "RST_CTRL_REG") (class "Default")
      (node (ref "U3") (pin "53") (pinfunction "PB14_53") (pintype "bidirectional"))
      (node (ref "U6") (pin "P1") (pinfunction "IO_L83N_VREF_3_P1") (pintype "bidirectional"))
    )
    (net (code "140") (name "RST_DATA_REG") (class "Default")
      (node (ref "U3") (pin "91") (pinfunction "PB5_91") (pintype "bidirectional"))
      (node (ref "U6") (pin "P144") (pinfunction "IO_L1P_HSWAPEN_0_P144") (pintype "bidirectional"))
    )
    (net (code "141") (name "SCK_LLS") (class "Default")
      (node (ref "MICRO_SD1") (pin "5") (pinfunction "CLK_5") (pintype "bidirectional"))
      (node (ref "R18") (pin "2") (pinfunction "2_2") (pintype "passive"))
    )
    (net (code "142") (name "SCL") (class "Default")
      (node (ref "U3") (pin "92") (pinfunction "PB6_92") (pintype "bidirectional"))
    )
    (net (code "143") (name "SCLK") (class "Default")
      (node (ref "R18") (pin "1") (pinfunction "1_1") (pintype "passive"))
      (node (ref "U3") (pin "30") (pinfunction "PA5_30") (pintype "bidirectional"))
    )
    (net (code "144") (name "SDA") (class "Default")
      (node (ref "U3") (pin "93") (pinfunction "PB7_93") (pintype "bidirectional"))
    )
    (net (code "145") (name "SD_LED") (class "Default")
      (node (ref "LED2") (pin "C") (pinfunction "C_C") (pintype "passive"))
      (node (ref "U3") (pin "15") (pinfunction "PC0_15") (pintype "bidirectional"))
    )
    (net (code "146") (name "SEL_128CHARS") (class "Default")
      (node (ref "U3") (pin "77") (pinfunction "PA15_77") (pintype "bidirectional"))
      (node (ref "U6") (pin "P141") (pinfunction "IO_L2N_0_P141") (pintype "bidirectional"))
    )
    (net (code "147") (name "SOUND") (class "Default")
      (node (ref "R1") (pin "2") (pinfunction "2_2") (pintype "passive"))
      (node (ref "U3") (pin "29") (pinfunction "PA4_29") (pintype "bidirectional"))
    )
    (net (code "148") (name "SOUND'") (class "Default")
      (node (ref "J4") (pin "2") (pinfunction "2_2") (pintype "passive"))
      (node (ref "J4") (pin "3") (pinfunction "3_3") (pintype "passive"))
      (node (ref "R1") (pin "1") (pinfunction "1_1") (pintype "passive"))
      (node (ref "R37") (pin "1") (pinfunction "1_1") (pintype "passive"))
      (node (ref "X1") (pin "2") (pinfunction "2_2") (pintype "passive"))
      (node (ref "X1") (pin "6") (pinfunction "6_6") (pintype "passive"))
    )
    (net (code "149") (name "SPARE") (class "Default")
      (node (ref "U6") (pin "P75") (pinfunction "IO_L74P_AWAKE_1_P75") (pintype "bidirectional"))
    )
    (net (code "150") (name "SS_SD") (class "Default")
      (node (ref "R21") (pin "1") (pinfunction "1_1") (pintype "passive"))
      (node (ref "U3") (pin "54") (pinfunction "PB15_54") (pintype "bidirectional"))
    )
    (net (code "151") (name "TCK") (class "Default")
      (node (ref "JP3") (pin "1") (pinfunction "1_1") (pintype "passive"))
      (node (ref "U6") (pin "P109") (pinfunction "TCK_P109") (pintype "bidirectional"))
    )
    (net (code "152") (name "TDI") (class "Default")
      (node (ref "JP3") (pin "3") (pinfunction "3_3") (pintype "passive"))
      (node (ref "U6") (pin "P110") (pinfunction "TDI_P110") (pintype "bidirectional"))
    )
    (net (code "153") (name "TDO") (class "Default")
      (node (ref "JP3") (pin "2") (pinfunction "2_2") (pintype "passive"))
      (node (ref "U6") (pin "P106") (pinfunction "TDO_P106") (pintype "bidirectional"))
    )
    (net (code "154") (name "TMS") (class "Default")
      (node (ref "JP3") (pin "4") (pinfunction "4_4") (pintype "passive"))
      (node (ref "U6") (pin "P107") (pinfunction "TMS_P107") (pintype "bidirectional"))
    )
    (net (code "155") (name "UART_RX") (class "Default")
      (node (ref "JP4") (pin "3") (pinfunction "3_3") (pintype "passive"))
      (node (ref "U3") (pin "69") (pinfunction "PA10_69") (pintype "bidirectional"))
    )
    (net (code "156") (name "UART_TX") (class "Default")
      (node (ref "JP4") (pin "4") (pinfunction "4_4") (pintype "passive"))
      (node (ref "U3") (pin "68") (pinfunction "PA9_68") (pintype "bidirectional"))
    )
    (net (code "157") (name "UP") (class "Default")
      (node (ref "J2") (pin "1") (pinfunction "1_1") (pintype "passive"))
      (node (ref "U6") (pin "P78") (pinfunction "IO_L47N_1_P78") (pintype "bidirectional"))
    )
    (net (code "158") (name "VCC") (class "Default")
      (node (ref "23B") (pin "1") (pinfunction "P_1") (pintype "passive"))
      (node (ref "2A") (pin "1") (pinfunction "P_1") (pintype "passive"))
      (node (ref "C3") (pin "1") (pinfunction "1_1") (pintype "passive"))
      (node (ref "C8") (pin "2") (pinfunction "2_2") (pintype "passive"))
      (node (ref "D1") (pin "C") (pinfunction "C_C") (pintype "passive"))
      (node (ref "D2") (pin "C") (pinfunction "C_C") (pintype "passive"))
      (node (ref "D4") (pin "C") (pinfunction "C_C") (pintype "passive"))
      (node (ref "IC2") (pin "3") (pinfunction "VIN_3") (pintype "input"))
      (node (ref "IC5") (pin "3") (pinfunction "VIN_3") (pintype "input"))
      (node (ref "JP4") (pin "1") (pinfunction "1_1") (pintype "passive"))
      (node (ref "JP6") (pin "1") (pinfunction "1_1") (pintype "passive"))
      (node (ref "R11") (pin "1") (pinfunction "1_1") (pintype "passive"))
      (node (ref "R15") (pin "2") (pinfunction "2_2") (pintype "passive"))
      (node (ref "R22") (pin "2") (pinfunction "2_2") (pintype "passive"))
      (node (ref "R7") (pin "2") (pinfunction "2_2") (pintype "passive"))
      (node (ref "U1") (pin "14") (pinfunction "DPOS_14") (pintype "power_in"))
      (node (ref "U1") (pin "15") (pinfunction "VSYNC_15") (pintype "input"))
      (node (ref "U1") (pin "4") (pinfunction "APOS_4") (pintype "power_in"))
      (node (ref "U1") (pin "5") (pinfunction "ENCD_5") (pintype "input"))
      (node (ref "U2") (pin "32") (pinfunction "VCC_32") (pintype "power_in"))
      (node (ref "U5") (pin "6") (pinfunction "VDD_6") (pintype "power_in"))
    )
    (net (code "159") (name "VCC_USB") (class "Default")
      (node (ref "D2") (pin "A") (pinfunction "A_A") (pintype "passive"))
      (node (ref "J3") (pin "A4_B9") (pinfunction "VBUS_A4_B9") (pintype "power_in"))
      (node (ref "J3") (pin "B4_A9") (pinfunction "VBUS_B4_A9") (pintype "power_in"))
    )
    (net (code "160") (name "VID_CLK") (class "Default")
      (node (ref "U1") (pin "3") (pinfunction "FIN_3") (pintype "input"))
      (node (ref "U6") (pin "P56") (pinfunction "IO_L30P_GCLK1_D13_2_P56") (pintype "bidirectional"))
    )
    (net (code "161") (name "V_BLUE") (class "Default")
      (node (ref "R29") (pin "1") (pinfunction "1_1") (pintype "passive"))
      (node (ref "U6") (pin "P9") (pinfunction "IO_L50N_3_P9") (pintype "bidirectional"))
    )
    (net (code "162") (name "V_BLUE'") (class "Default")
      (node (ref "R28") (pin "1") (pinfunction "1_1") (pintype "passive"))
      (node (ref "R8") (pin "1") (pinfunction "1_1") (pintype "passive"))
      (node (ref "U1") (pin "8") (pinfunction "BIN_8") (pintype "input"))
      (node (ref "X1") (pin "7") (pinfunction "7_7") (pintype "passive"))
    )
    (net (code "163") (name "V_GREEN") (class "Default")
      (node (ref "R31") (pin "1") (pinfunction "1_1") (pintype "passive"))
      (node (ref "U6") (pin "P8") (pinfunction "IO_L51P_3_P8") (pintype "bidirectional"))
    )
    (net (code "164") (name "V_GREEN'") (class "Default")
      (node (ref "R27") (pin "1") (pinfunction "1_1") (pintype "passive"))
      (node (ref "R9") (pin "1") (pinfunction "1_1") (pintype "passive"))
      (node (ref "U1") (pin "7") (pinfunction "GIN_7") (pintype "input"))
      (node (ref "X1") (pin "11") (pinfunction "11_11") (pintype "passive"))
    )
    (net (code "165") (name "V_RED") (class "Default")
      (node (ref "R32") (pin "1") (pinfunction "1_1") (pintype "passive"))
      (node (ref "U6") (pin "P7") (pinfunction "IO_L51N_3_P7") (pintype "bidirectional"))
    )
    (net (code "166") (name "V_RED'") (class "Default")
      (node (ref "R10") (pin "1") (pinfunction "1_1") (pintype "passive"))
      (node (ref "R19") (pin "1") (pinfunction "1_1") (pintype "passive"))
      (node (ref "U1") (pin "6") (pinfunction "RIN_6") (pintype "input"))
      (node (ref "X1") (pin "15") (pinfunction "15_15") (pintype "passive"))
    )
    (net (code "167") (name "unconnected-(J2-Pad5)") (class "Default")
      (node (ref "J2") (pin "5") (pinfunction "5_5") (pintype "passive"))
    )
    (net (code "168") (name "unconnected-(J2-Pad7)") (class "Default")
      (node (ref "J2") (pin "7") (pinfunction "7_7") (pintype "passive"))
    )
    (net (code "169") (name "unconnected-(J2-Pad9)") (class "Default")
      (node (ref "J2") (pin "9") (pinfunction "9_9") (pintype "passive"))
    )
    (net (code "170") (name "unconnected-(MICRO_SD1-CD-PadCD1)") (class "Default")
      (node (ref "MICRO_SD1") (pin "CD1") (pinfunction "CD_CD1") (pintype "passive"))
    )
    (net (code "171") (name "unconnected-(MICRO_SD1-DAT1-Pad8)") (class "Default")
      (node (ref "MICRO_SD1") (pin "8") (pinfunction "DAT1_8") (pintype "bidirectional"))
    )
    (net (code "172") (name "unconnected-(MICRO_SD1-DAT2-Pad1)") (class "Default")
      (node (ref "MICRO_SD1") (pin "1") (pinfunction "DAT2_1") (pintype "bidirectional"))
    )
    (net (code "173") (name "unconnected-(U1-CRMA-Pad9)") (class "Default")
      (node (ref "U1") (pin "9") (pinfunction "CRMA_9") (pintype "output"))
    )
    (net (code "174") (name "unconnected-(U1-LUMA-Pad11)") (class "Default")
      (node (ref "U1") (pin "11") (pinfunction "LUMA_11") (pintype "output"))
    )
    (net (code "175") (name "unconnected-(U3-PB8-Pad95)") (class "Default")
      (node (ref "U3") (pin "95") (pinfunction "PB8_95") (pintype "bidirectional"))
    )
    (net (code "176") (name "unconnected-(U3-PC2-Pad17)") (class "Default")
      (node (ref "U3") (pin "17") (pinfunction "PC2_17") (pintype "bidirectional"))
    )
    (net (code "177") (name "unconnected-(U3-PC3-Pad18)") (class "Default")
      (node (ref "U3") (pin "18") (pinfunction "PC3_18") (pintype "bidirectional"))
    )
    (net (code "178") (name "unconnected-(U3-PC4-Pad33)") (class "Default")
      (node (ref "U3") (pin "33") (pinfunction "PC4_33") (pintype "bidirectional"))
    )
    (net (code "179") (name "unconnected-(U3-PC5-Pad34)") (class "Default")
      (node (ref "U3") (pin "34") (pinfunction "PC5_34") (pintype "bidirectional"))
    )
    (net (code "180") (name "unconnected-(U5-NC-Pad2)") (class "Default")
      (node (ref "U5") (pin "2") (pinfunction "NC_2") (pintype "no_connect"))
    )
    (net (code "181") (name "unconnected-(U6-CMPCS_B_2-PadP72)") (class "Default")
      (node (ref "U6") (pin "P72") (pinfunction "CMPCS_B_2_P72") (pintype "bidirectional"))
    )
    (net (code "182") (name "unconnected-(U6-DONE_2-PadP71)") (class "Default")
      (node (ref "U6") (pin "P71") (pinfunction "DONE_2_P71") (pintype "bidirectional"))
    )
    (net (code "183") (name "unconnected-(X1-Pad1)") (class "Default")
      (node (ref "X1") (pin "1") (pinfunction "1_1") (pintype "passive"))
    )
    (net (code "184") (name "unconnected-(X1-Pad3)") (class "Default")
      (node (ref "X1") (pin "3") (pinfunction "3_3") (pintype "passive"))
    )
    (net (code "185") (name "unconnected-(X1-Pad10)") (class "Default")
      (node (ref "X1") (pin "10") (pinfunction "10_10") (pintype "passive"))
    )
    (net (code "186") (name "unconnected-(X1-Pad12)") (class "Default")
      (node (ref "X1") (pin "12") (pinfunction "12_12") (pintype "passive"))
    )
    (net (code "187") (name "unconnected-(X1-Pad19)") (class "Default")
      (node (ref "X1") (pin "19") (pinfunction "19_19") (pintype "passive"))
    )
    (net (code "188") (name "{slash}BUSAK") (class "Default")
      (node (ref "18A") (pin "1") (pinfunction "P_1") (pintype "passive"))
    )
    (net (code "189") (name "{slash}BUSRQ") (class "Default")
      (node (ref "20A") (pin "1") (pinfunction "P_1") (pintype "passive"))
    )
    (net (code "190") (name "{slash}CLOCK") (class "Default")
      (node (ref "6B") (pin "1") (pinfunction "P_1") (pintype "passive"))
      (node (ref "U6") (pin "P24") (pinfunction "IO_L41P_GCLK27_3_P24") (pintype "bidirectional"))
    )
    (net (code "191") (name "{slash}HALT") (class "Default")
      (node (ref "13A") (pin "1") (pinfunction "P_1") (pintype "passive"))
      (node (ref "U6") (pin "P46") (pinfunction "IO_L49P_D3_2_P46") (pintype "bidirectional"))
    )
    (net (code "192") (name "{slash}IORQ") (class "Default")
      (node (ref "15A") (pin "1") (pinfunction "P_1") (pintype "passive"))
      (node (ref "U6") (pin "P51") (pinfunction "IO_L31P_GCLK31_D14_2_P51") (pintype "bidirectional"))
    )
    (net (code "193") (name "{slash}M1") (class "Default")
      (node (ref "22A") (pin "1") (pinfunction "P_1") (pintype "passive"))
      (node (ref "U6") (pin "P67") (pinfunction "IO_L2P_CMPCLK_2_P67") (pintype "bidirectional"))
    )
    (net (code "194") (name "{slash}MEM_OE") (class "Default")
      (node (ref "U2") (pin "24") (pinfunction "OE_24") (pintype "input"))
      (node (ref "U6") (pin "P92") (pinfunction "IO_L41N_GCLK8_1_P92") (pintype "bidirectional"))
    )
    (net (code "195") (name "{slash}MREQ") (class "Default")
      (node (ref "14A") (pin "1") (pinfunction "P_1") (pintype "passive"))
      (node (ref "U6") (pin "P48") (pinfunction "IO_L48P_D7_2_P48") (pintype "bidirectional"))
    )
    (net (code "196") (name "{slash}NMI") (class "Default")
      (node (ref "12A") (pin "1") (pinfunction "P_1") (pintype "passive"))
      (node (ref "U6") (pin "P44") (pinfunction "IO_L62P_D5_2_P44") (pintype "bidirectional"))
    )
    (net (code "197") (name "{slash}OE_OL") (class "Default")
      (node (ref "U3") (pin "47") (pinfunction "PB10_47") (pintype "bidirectional"))
      (node (ref "U6") (pin "P12") (pinfunction "IO_L49P_3_P12") (pintype "bidirectional"))
    )
    (net (code "198") (name "{slash}RD") (class "Default")
      (node (ref "16A") (pin "1") (pinfunction "P_1") (pintype "passive"))
      (node (ref "U6") (pin "P105") (pinfunction "IO_L1P_1_P105") (pintype "bidirectional"))
    )
    (net (code "199") (name "{slash}RESET") (class "Default")
      (node (ref "21A") (pin "1") (pinfunction "P_1") (pintype "passive"))
      (node (ref "U3") (pin "96") (pinfunction "PB9_96") (pintype "bidirectional"))
      (node (ref "U6") (pin "P139") (pinfunction "IO_L3N_0_P139") (pintype "bidirectional"))
    )
    (net (code "200") (name "{slash}RFSH") (class "Default")
      (node (ref "23A") (pin "1") (pinfunction "P_1") (pintype "passive"))
      (node (ref "U6") (pin "P74") (pinfunction "IO_L74N_DOUT_BUSY_1_P74") (pintype "bidirectional"))
    )
    (net (code "201") (name "{slash}WAIT") (class "Default")
      (node (ref "19A") (pin "1") (pinfunction "P_1") (pintype "passive"))
      (node (ref "U3") (pin "23") (pinfunction "PA0_23") (pintype "bidirectional"))
    )
    (net (code "202") (name "{slash}WR") (class "Default")
      (node (ref "17A") (pin "1") (pinfunction "P_1") (pintype "passive"))
      (node (ref "U6") (pin "P58") (pinfunction "IO_L14P_D11_2_P58") (pintype "bidirectional"))
    )
    (net (code "203") (name "{slash}WR'") (class "Default")
      (node (ref "U2") (pin "29") (pinfunction "WE_29") (pintype "input"))
      (node (ref "U3") (pin "26") (pinfunction "PA3_26") (pintype "bidirectional"))
      (node (ref "U6") (pin "P102") (pinfunction "IO_L32P_1_P102") (pintype "bidirectional"))
    )
  )
)
